# BalanceCar_sch.net
KiCad netlist of a schematic drawn in Altium Designer
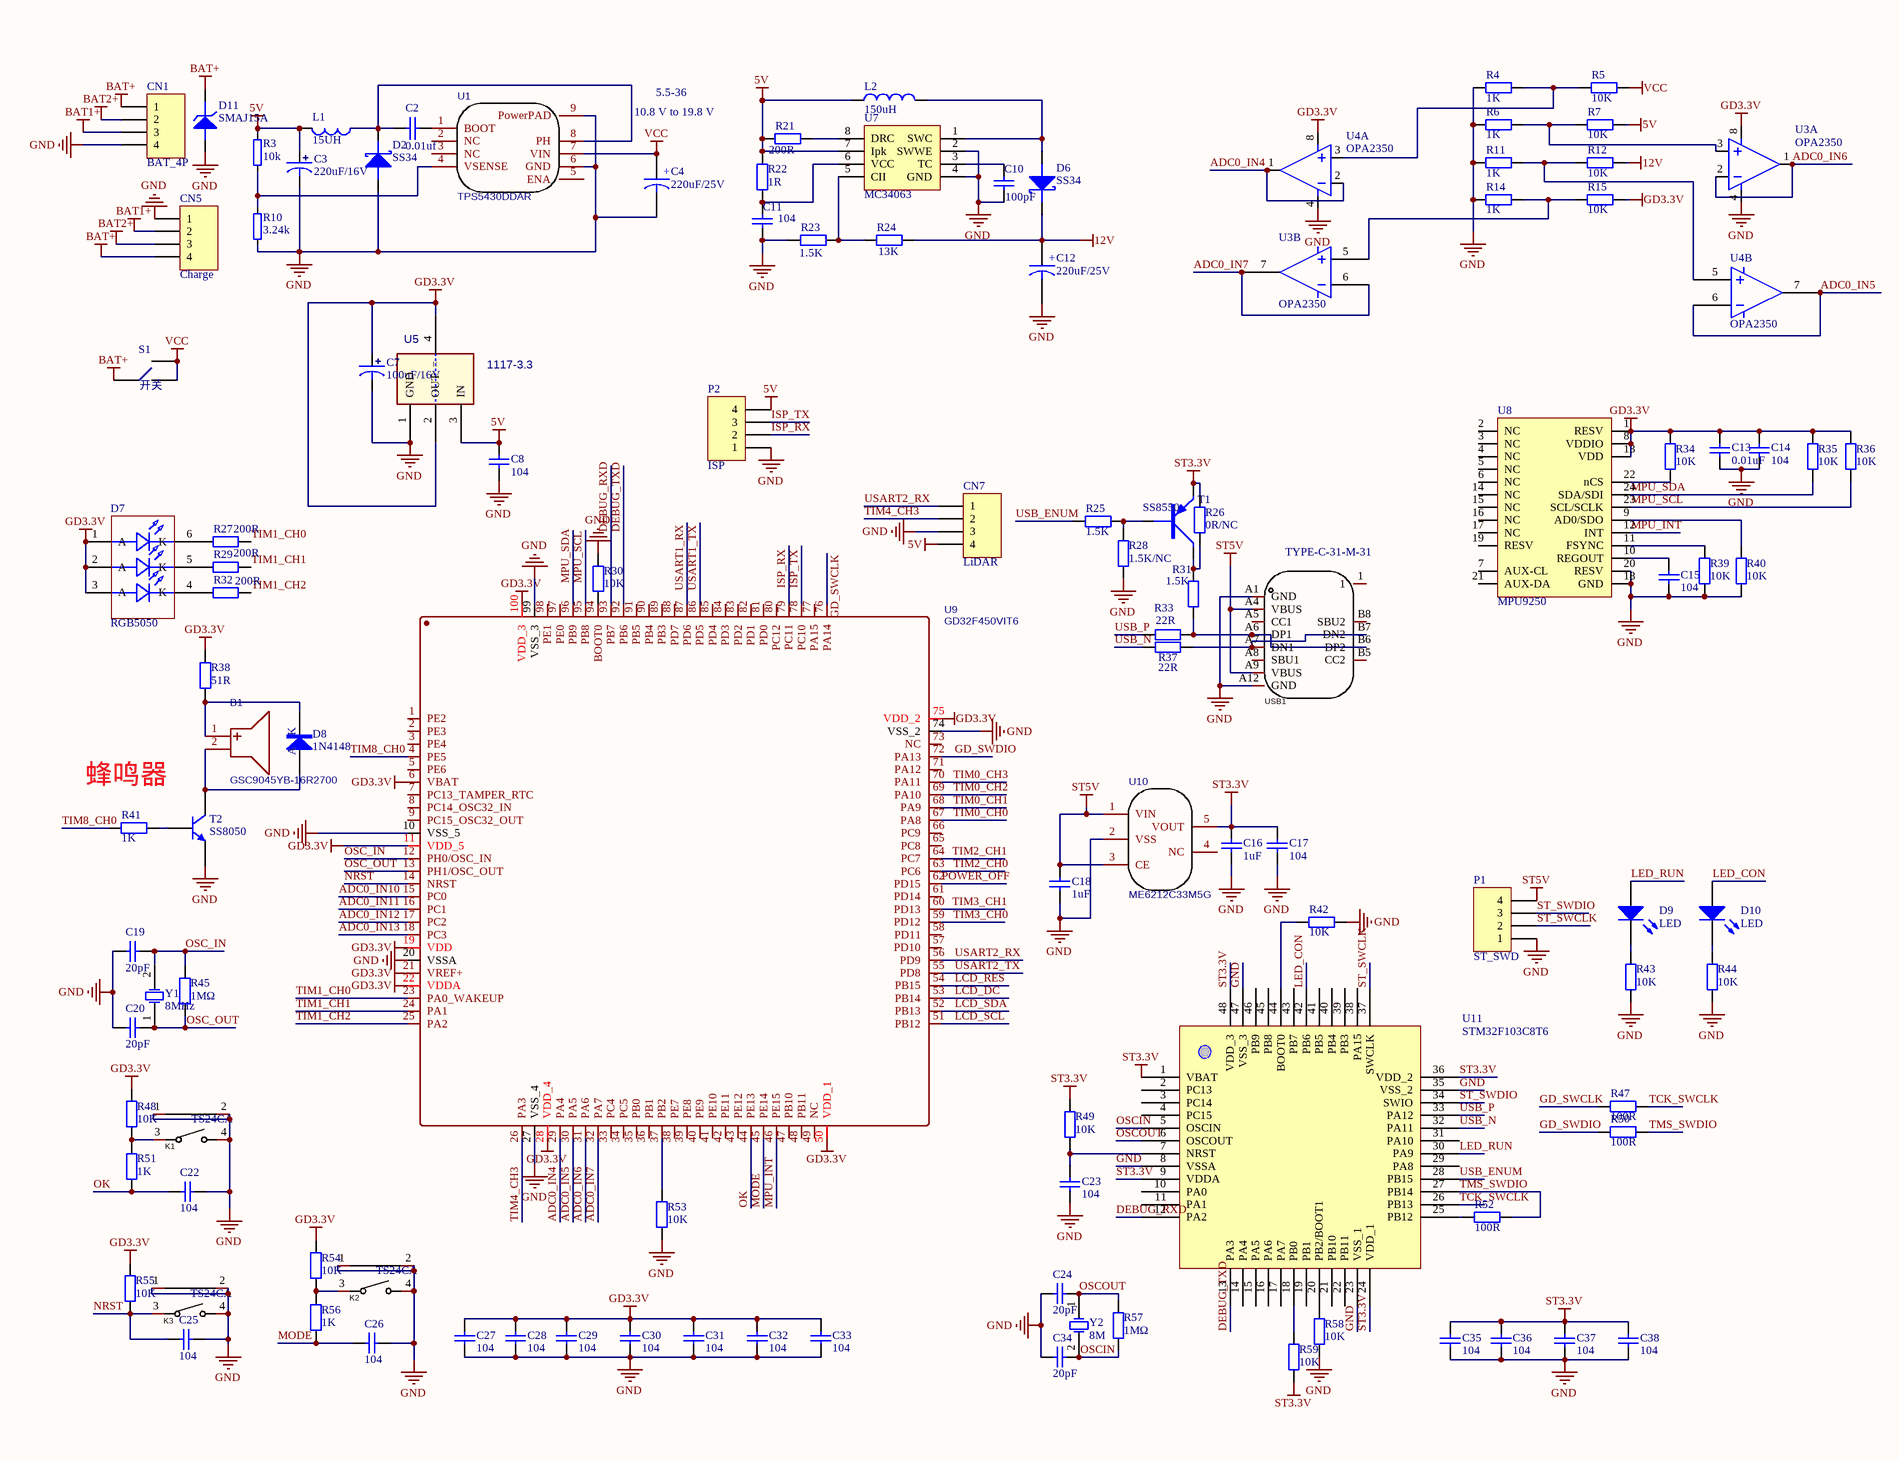
[diagram p0: BalanceCar_sch.SchDoc, left]
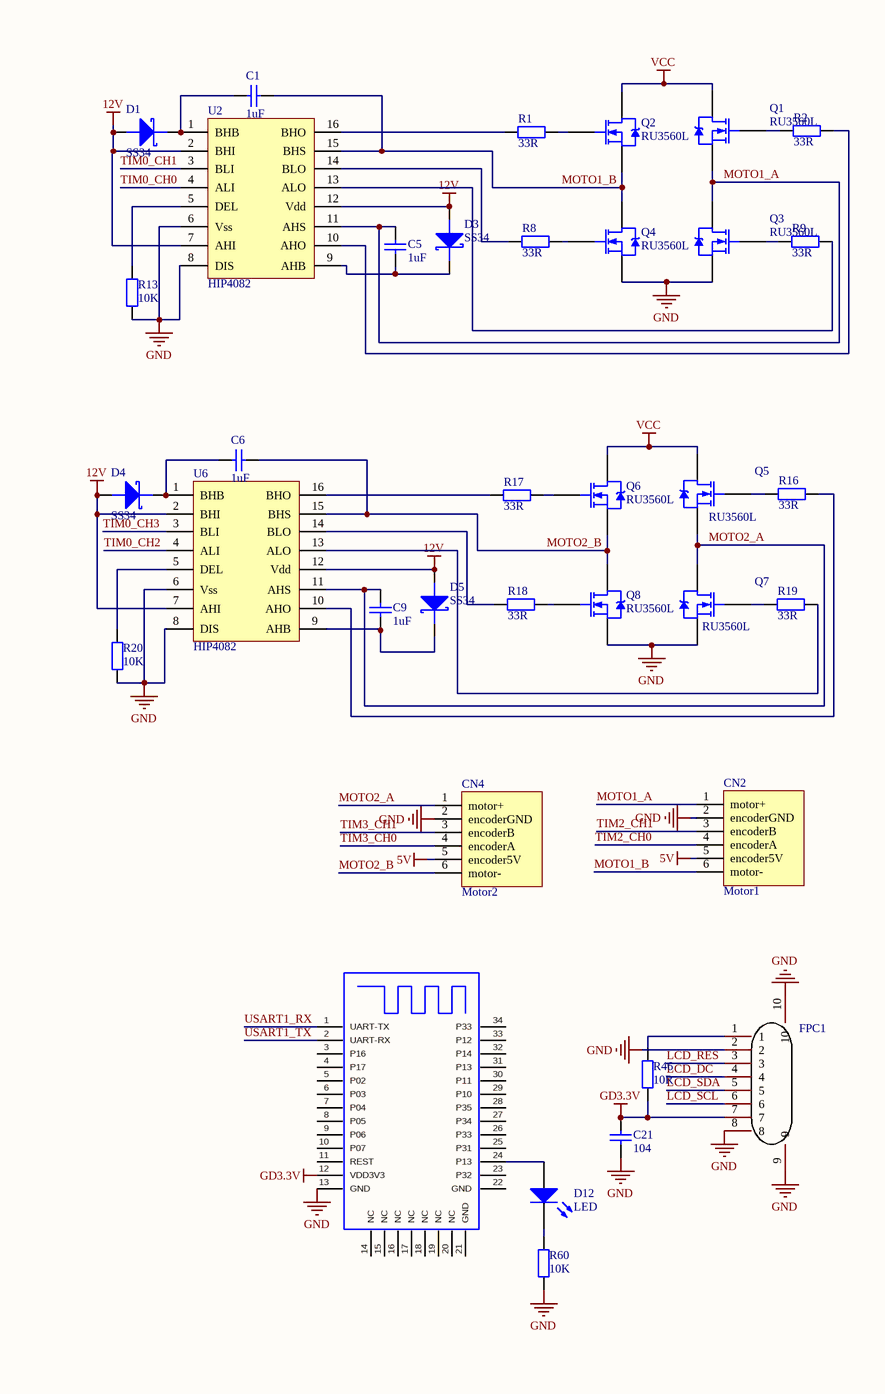
[diagram p1: BalanceCar_sch.SchDoc, right]

(export (version "E")
  (design (tool "Eeschema 10.0.6"))
  (components
    (comp (ref "B1")
      (value "GSC9045YB-16R2700")
      (footprint "BUZ-SMD_GSC9045YB-16R2700")
      (description "无源蜂鸣器")
      (fields (field (name "BOM_SUPPLIER PART") "C255324") (field (name "CONTRIBUTOR") "LCSC"))
      (libsource (lib "1") (part "GSC9045YB-16R2700"))
    )
    (comp (ref "C1")
      (value "1uF")
      (footprint "0603-JLC-C")
      (description "C0603")
      (fields (field (name "PUBLISHER") "Altium Limited"))
      (libsource (lib "Miscellaneous Devices") (part "Cap"))
    )
    (comp (ref "C2")
      (value "0.01uf")
      (footprint "0603-JLC-C")
      (description "C0603")
      (libsource (lib "电容") (part "普通电容"))
    )
    (comp (ref "C3")
      (value "220uF/16V")
      (footprint "SMD,6.3x5.3mm")
      (description "6.3*5.3mm铝电解电容")
      (libsource (lib "电容") (part "SMD_ECAP"))
    )
    (comp (ref "C4")
      (value "220uF/25V")
      (footprint "SMD,6.3x5.8mm")
      (description "贴片铝电解电容SMD,6.3x5.8mm")
      (libsource (lib "*") (part "CAP极性"))
    )
    (comp (ref "C5")
      (value "1uF")
      (footprint "0603-JLC-C")
      (description "C0603")
      (fields (field (name "PUBLISHER") "Altium Limited"))
      (libsource (lib "Miscellaneous Devices") (part "Cap"))
    )
    (comp (ref "C6")
      (value "1uF")
      (footprint "0603-JLC-C")
      (description "C0603")
      (fields (field (name "PUBLISHER") "Altium Limited"))
      (libsource (lib "Miscellaneous Devices") (part "Cap"))
    )
    (comp (ref "C7")
      (value "100uF/16V")
      (footprint "SMD,6.3x5.3mm")
      (description "6.3*5.3mm铝电解电容")
      (libsource (lib "电容") (part "SMD_ECAP"))
    )
    (comp (ref "C8")
      (value "104")
      (footprint "0603-JLC-C")
      (description "C0603")
      (fields (field (name "PUBLISHER") "Altium Limited"))
      (libsource (lib "Miscellaneous Devices") (part "Cap"))
    )
    (comp (ref "C9")
      (value "1uF")
      (footprint "0603-JLC-C")
      (description "C0603")
      (fields (field (name "PUBLISHER") "Altium Limited"))
      (libsource (lib "Miscellaneous Devices") (part "Cap"))
    )
    (comp (ref "C10") (value "100pF") (footprint "0603-JLC-C") (libsource (lib "Luo") (part "CAP_0805")))
    (comp (ref "C11") (value "104") (footprint "0603-JLC-C") (libsource (lib "Luo") (part "CAP_0805")))
    (comp (ref "C12")
      (value "220uF/25V")
      (footprint "SMD,6.3x5.8mm")
      (description "贴片铝电解电容SMD,6.3x5.8mm")
      (libsource (lib "*") (part "CAP极性"))
    )
    (comp (ref "C13")
      (value "0.01uF")
      (footprint "0603-JLC-C")
      (description "C0603")
      (fields (field (name "PUBLISHER") "Altium Limited"))
      (libsource (lib "Miscellaneous Devices") (part "Cap"))
    )
    (comp (ref "C14")
      (value "104")
      (footprint "0603-JLC-C")
      (description "C0603")
      (fields (field (name "PUBLISHER") "Altium Limited"))
      (libsource (lib "Miscellaneous Devices") (part "Cap"))
    )
    (comp (ref "C15")
      (value "104")
      (footprint "0603-JLC-C")
      (description "C0603")
      (fields (field (name "PUBLISHER") "Altium Limited"))
      (libsource (lib "Miscellaneous Devices") (part "Cap"))
    )
    (comp (ref "C16")
      (value "1uF")
      (footprint "0603-JLC-C")
      (description "C0603")
      (fields (field (name "PUBLISHER") "Altium Limited"))
      (libsource (lib "Miscellaneous Devices") (part "Cap"))
    )
    (comp (ref "C17")
      (value "104")
      (footprint "0603-JLC-C")
      (description "C0603")
      (fields (field (name "PUBLISHER") "Altium Limited"))
      (libsource (lib "Miscellaneous Devices") (part "Cap"))
    )
    (comp (ref "C18")
      (value "1uF")
      (footprint "0603-JLC-C")
      (description "C0603")
      (fields (field (name "PUBLISHER") "Altium Limited"))
      (libsource (lib "Miscellaneous Devices") (part "Cap"))
    )
    (comp (ref "C19")
      (value "20pF")
      (footprint "0603-JLC-C")
      (description "C0603")
      (fields (field (name "PUBLISHER") "Altium Limited"))
      (libsource (lib "Miscellaneous Devices") (part "Cap"))
    )
    (comp (ref "C20")
      (value "20pF")
      (footprint "0603-JLC-C")
      (description "C0603")
      (fields (field (name "PUBLISHER") "Altium Limited"))
      (libsource (lib "Miscellaneous Devices") (part "Cap"))
    )
    (comp (ref "C21")
      (value "104")
      (footprint "0603-JLC-C")
      (description "C0603")
      (fields (field (name "PUBLISHER") "Altium Limited"))
      (libsource (lib "Miscellaneous Devices") (part "Cap"))
    )
    (comp (ref "C22")
      (value "104")
      (footprint "0603-JLC-C")
      (description "C0603")
      (fields (field (name "PUBLISHER") "Altium Limited"))
      (libsource (lib "Miscellaneous Devices") (part "Cap"))
    )
    (comp (ref "C23")
      (value "104")
      (footprint "0603-JLC-C")
      (description "C0603")
      (fields (field (name "PUBLISHER") "Altium Limited"))
      (libsource (lib "Miscellaneous Devices") (part "Cap"))
    )
    (comp (ref "C24")
      (value "20pF")
      (footprint "0603-JLC-C")
      (description "C0603")
      (fields (field (name "PUBLISHER") "Altium Limited"))
      (libsource (lib "STM32F103C8T6") (part "Cap"))
    )
    (comp (ref "C25")
      (value "104")
      (footprint "0603-JLC-C")
      (description "C0603")
      (fields (field (name "PUBLISHER") "Altium Limited"))
      (libsource (lib "Miscellaneous Devices") (part "Cap"))
    )
    (comp (ref "C26")
      (value "104")
      (footprint "0603-JLC-C")
      (description "C0603")
      (fields (field (name "PUBLISHER") "Altium Limited"))
      (libsource (lib "Miscellaneous Devices") (part "Cap"))
    )
    (comp (ref "C27")
      (value "104")
      (footprint "0603-JLC-C")
      (description "C0603")
      (fields (field (name "PUBLISHER") "Altium Limited"))
      (libsource (lib "Miscellaneous Devices") (part "Cap"))
    )
    (comp (ref "C28")
      (value "104")
      (footprint "0603-JLC-C")
      (description "C0603")
      (fields (field (name "PUBLISHER") "Altium Limited"))
      (libsource (lib "Miscellaneous Devices") (part "Cap"))
    )
    (comp (ref "C29")
      (value "104")
      (footprint "0603-JLC-C")
      (description "C0603")
      (fields (field (name "PUBLISHER") "Altium Limited"))
      (libsource (lib "Miscellaneous Devices") (part "Cap"))
    )
    (comp (ref "C30")
      (value "104")
      (footprint "0603-JLC-C")
      (description "C0603")
      (fields (field (name "PUBLISHER") "Altium Limited"))
      (libsource (lib "Miscellaneous Devices") (part "Cap"))
    )
    (comp (ref "C31")
      (value "104")
      (footprint "0603-JLC-C")
      (description "C0603")
      (fields (field (name "PUBLISHER") "Altium Limited"))
      (libsource (lib "Miscellaneous Devices") (part "Cap"))
    )
    (comp (ref "C32")
      (value "104")
      (footprint "0603-JLC-C")
      (description "C0603")
      (fields (field (name "PUBLISHER") "Altium Limited"))
      (libsource (lib "Miscellaneous Devices") (part "Cap"))
    )
    (comp (ref "C33")
      (value "104")
      (footprint "0603-JLC-C")
      (description "C0603")
      (fields (field (name "PUBLISHER") "Altium Limited"))
      (libsource (lib "Miscellaneous Devices") (part "Cap"))
    )
    (comp (ref "C34")
      (value "20pF")
      (footprint "0603-JLC-C")
      (description "C0603")
      (fields (field (name "PUBLISHER") "Altium Limited"))
      (libsource (lib "STM32F103C8T6") (part "Cap"))
    )
    (comp (ref "C35")
      (value "104")
      (footprint "0603-JLC-C")
      (description "C0603")
      (fields (field (name "PUBLISHER") "Altium Limited"))
      (libsource (lib "Miscellaneous Devices") (part "Cap"))
    )
    (comp (ref "C36")
      (value "104")
      (footprint "0603-JLC-C")
      (description "C0603")
      (fields (field (name "PUBLISHER") "Altium Limited"))
      (libsource (lib "Miscellaneous Devices") (part "Cap"))
    )
    (comp (ref "C37")
      (value "104")
      (footprint "0603-JLC-C")
      (description "C0603")
      (fields (field (name "PUBLISHER") "Altium Limited"))
      (libsource (lib "Miscellaneous Devices") (part "Cap"))
    )
    (comp (ref "C38")
      (value "104")
      (footprint "0603-JLC-C")
      (description "C0603")
      (fields (field (name "PUBLISHER") "Altium Limited"))
      (libsource (lib "Miscellaneous Devices") (part "Cap"))
    )
    (comp (ref "CN1")
      (value "BAT_4P")
      (footprint "CONN-TH_4P-P2.50_HX25003-4A")
      (description "卧式XH2.54 4P")
      (fields (field (name "PUBLISHER") "Altium Limited"))
      (libsource (lib "Miscellaneous Connectors") (part "Header 4"))
    )
    (comp (ref "CN2")
      (value "Motor1")
      (footprint "CONN-TH_6P-P2.50_X8821WR-06S-N2SN")
      (description "卧式XH2.54 6P")
      (libsource (lib "Schlib1") (part "Motor"))
    )
    (comp (ref "CN4")
      (value "Motor2")
      (footprint "CONN-TH_6P-P2.50_X8821WR-06S-N2SN")
      (description "卧式XH2.54 6P")
      (libsource (lib "Schlib1") (part "Motor"))
    )
    (comp (ref "CN5")
      (value "Charge")
      (footprint "CONN-TH_4P-P2.54_X8821WR-06S-N2SN")
      (description "卧式XH2.54 4P")
      (fields (field (name "PUBLISHER") "Altium Limited"))
      (libsource (lib "Miscellaneous Connectors") (part "Header 4"))
    )
    (comp (ref "CN7")
      (value "LiDAR")
      (footprint "CONN-TH_4P-P2.50_HX25003-4A")
      (description "卧式XH2.54 4P")
      (fields (field (name "PUBLISHER") "Altium Limited"))
      (libsource (lib "Miscellaneous Connectors") (part "Header 4"))
    )
    (comp (ref "D1")
      (value "SS34")
      (footprint "SMA(DO-214AC)")
      (description "肖特基二极管")
      (libsource (lib "二极管") (part "DIODE SCHOTTKY"))
    )
    (comp (ref "D2")
      (value "SS34")
      (footprint "SMA(DO-214AC)")
      (description "肖特基二极管")
      (libsource (lib "二极管") (part "DIODE SCHOTTKY"))
    )
    (comp (ref "D3")
      (value "SS34")
      (footprint "SMA(DO-214AC)")
      (description "肖特基二极管")
      (libsource (lib "二极管") (part "DIODE SCHOTTKY"))
    )
    (comp (ref "D4")
      (value "SS34")
      (footprint "SMA(DO-214AC)")
      (description "肖特基二极管")
      (libsource (lib "二极管") (part "DIODE SCHOTTKY"))
    )
    (comp (ref "D5")
      (value "SS34")
      (footprint "SMA(DO-214AC)")
      (description "肖特基二极管")
      (libsource (lib "二极管") (part "DIODE SCHOTTKY"))
    )
    (comp (ref "D6")
      (value "SS34")
      (footprint "SMA(DO-214AC)")
      (description "肖特基二极管")
      (libsource (lib "二极管") (part "DIODE SCHOTTKY"))
    )
    (comp (ref "D7")
      (value "RGB5050")
      (footprint "LED-SMD_6P-L5.0-W5.0-FD")
      (description "5050灯珠")
      (libsource (lib "Pathfinder_pcb") (part "RGB5050"))
    )
    (comp (ref "D8")
      (value "1N4148")
      (footprint "1206")
      (description "Diode")
      (libsource (lib "*") (part "DIODE"))
    )
    (comp (ref "D9")
      (value "LED")
      (footprint "0603LED")
      (description "0603白色LED")
      (fields (field (name "PUBLISHER") "Altium Limited"))
      (libsource (lib "running car pcb") (part "LED3"))
    )
    (comp (ref "D10")
      (value "LED")
      (footprint "0603LED")
      (description "0603白色LED")
      (fields (field (name "PUBLISHER") "Altium Limited"))
      (libsource (lib "running car pcb") (part "LED3"))
    )
    (comp (ref "D11")
      (value "SMAJ15A")
      (footprint "SMA(DO-214AC)")
      (description "单向TVS管")
      (libsource (lib "Pathfinder_pcb") (part "DIODE ZENER"))
    )
    (comp (ref "D12")
      (value "LED")
      (footprint "0603LED")
      (description "0603白色LED")
      (fields (field (name "PUBLISHER") "Altium Limited"))
      (libsource (lib "running car pcb") (part "LED3"))
    )
    (comp (ref "FPC1")
      (value "AFC24-S08FIC-00")
      (footprint "FPC-SMD_P0.50-8P-QCHF-SM-H2.0")
      (description "间距:0.5mm;触点数量:8;锁定特性:翻盖式;安装类型:卧贴;触点类型:双侧触点/上下接;")
      (fields (field (name "MANUFACTURER") "JS(钜硕电子)"))
      (libsource (lib "altium-import") (part "root_0_AFC24-S08FIC-00_"))
    )
    (comp (ref "K1")
      (value "TS24CA")
      (footprint "SW-SMD_TS24CA")
      (fields (field (name "MANUFACTURER") "SHOU HAN(首韩)"))
      (libsource (lib "TS24CA1_TS24CA") (part "TS24CA"))
    )
    (comp (ref "K2")
      (value "TS24CA")
      (footprint "SW-SMD_TS24CA")
      (fields (field (name "MANUFACTURER") "SHOU HAN(首韩)"))
      (libsource (lib "TS24CA1_TS24CA") (part "TS24CA"))
    )
    (comp (ref "K3")
      (value "TS24CA")
      (footprint "SW-SMD_TS24CA")
      (fields (field (name "MANUFACTURER") "SHOU HAN(首韩)"))
      (libsource (lib "TS24CA1_TS24CA") (part "TS24CA"))
    )
    (comp (ref "L1")
      (value "15UH")
      (footprint "IND-SMD_L7.1-W6.6")
      (description "一体成型功率电感")
      (libsource (lib "常用元件库") (part "L"))
    )
    (comp (ref "L2")
      (value "150uH")
      (footprint "IND-SMD_L5.0-W5.0_SMNR5040")
      (description "Inductor")
      (fields (field (name "PUBLISHER") "Altium Limited"))
      (libsource (lib "Luo") (part "Inductor"))
    )
    (comp (ref "P1")
      (value "ST_SWD")
      (footprint "HDR1X4")
      (description "Header, 4-Pin")
      (fields (field (name "PUBLISHER") "Altium Limited"))
      (libsource (lib "") (part "Header 4_1"))
    )
    (comp (ref "P2")
      (value "ISP")
      (footprint "HDR1X4")
      (description "Header, 4-Pin")
      (fields (field (name "PUBLISHER") "Altium Limited"))
      (libsource (lib "") (part "Header 4_1"))
    )
    (comp (ref "Q1")
      (value "RU3560L")
      (footprint "TO-252-3L")
      (description "NMOSFET")
      (fields
        (field (name "MANUFACTURER") "International Rectifier")
        (field (name "PUBLISHER") "Altium Limited")
      )
      (libsource (lib "DMESC_1") (part "IRFR1205"))
    )
    (comp (ref "Q2")
      (value "RU3560L")
      (footprint "TO-252-3L")
      (description "NMOSFET")
      (fields
        (field (name "MANUFACTURER") "International Rectifier")
        (field (name "PUBLISHER") "Altium Limited")
      )
      (libsource (lib "DMESC_1") (part "IRFR1205"))
    )
    (comp (ref "Q3")
      (value "RU3560L")
      (footprint "TO-252-3L")
      (description "NMOSFET")
      (fields
        (field (name "MANUFACTURER") "International Rectifier")
        (field (name "PUBLISHER") "Altium Limited")
      )
      (libsource (lib "DMESC_1") (part "IRFR1205"))
    )
    (comp (ref "Q4")
      (value "RU3560L")
      (footprint "TO-252-3L")
      (description "NMOSFET")
      (fields
        (field (name "MANUFACTURER") "International Rectifier")
        (field (name "PUBLISHER") "Altium Limited")
      )
      (libsource (lib "DMESC_1") (part "IRFR1205"))
    )
    (comp (ref "Q5")
      (value "RU3560L")
      (footprint "TO-252-3L")
      (description "NMOSFET")
      (fields
        (field (name "MANUFACTURER") "International Rectifier")
        (field (name "PUBLISHER") "Altium Limited")
      )
      (libsource (lib "DMESC_1") (part "IRFR1205"))
    )
    (comp (ref "Q6")
      (value "RU3560L")
      (footprint "TO-252-3L")
      (description "NMOSFET")
      (fields
        (field (name "MANUFACTURER") "International Rectifier")
        (field (name "PUBLISHER") "Altium Limited")
      )
      (libsource (lib "DMESC_1") (part "IRFR1205"))
    )
    (comp (ref "Q7")
      (value "RU3560L")
      (footprint "TO-252-3L")
      (description "NMOSFET")
      (fields
        (field (name "MANUFACTURER") "International Rectifier")
        (field (name "PUBLISHER") "Altium Limited")
      )
      (libsource (lib "DMESC_1") (part "IRFR1205"))
    )
    (comp (ref "Q8")
      (value "RU3560L")
      (footprint "TO-252-3L")
      (description "NMOSFET")
      (fields
        (field (name "MANUFACTURER") "International Rectifier")
        (field (name "PUBLISHER") "Altium Limited")
      )
      (libsource (lib "DMESC_1") (part "IRFR1205"))
    )
    (comp (ref "R1")
      (value "33R")
      (footprint "0603-RMOS")
      (description "R0603")
      (fields (field (name "PUBLISHER") "Altium Limited"))
      (libsource (lib "") (part "Res2_3"))
    )
    (comp (ref "R2")
      (value "33R")
      (footprint "0603-RMOS")
      (description "R0603")
      (fields (field (name "PUBLISHER") "Altium Limited"))
      (libsource (lib "") (part "Res2_3"))
    )
    (comp (ref "R3")
      (value "10k")
      (footprint "0603-JLC-R")
      (description "R0603")
      (libsource (lib "电阻") (part "RES"))
    )
    (comp (ref "R4")
      (value "1K")
      (footprint "0603-JLC-R")
      (description "R0603")
      (fields (field (name "PUBLISHER") "Altium Limited"))
      (libsource (lib "Miscellaneous Devices") (part "Res2"))
    )
    (comp (ref "R5")
      (value "10K")
      (footprint "0603-JLC-R")
      (description "R0603")
      (fields (field (name "PUBLISHER") "Altium Limited"))
      (libsource (lib "Miscellaneous Devices") (part "Res2"))
    )
    (comp (ref "R6")
      (value "1K")
      (footprint "0603-JLC-R")
      (description "R0603")
      (fields (field (name "PUBLISHER") "Altium Limited"))
      (libsource (lib "Miscellaneous Devices") (part "Res2"))
    )
    (comp (ref "R7")
      (value "10K")
      (footprint "0603-JLC-R")
      (description "R0603")
      (fields (field (name "PUBLISHER") "Altium Limited"))
      (libsource (lib "Miscellaneous Devices") (part "Res2"))
    )
    (comp (ref "R8")
      (value "33R")
      (footprint "0603-RMOS")
      (description "R0603")
      (fields (field (name "PUBLISHER") "Altium Limited"))
      (libsource (lib "") (part "Res2_3"))
    )
    (comp (ref "R9")
      (value "33R")
      (footprint "0603-RMOS")
      (description "R0603")
      (fields (field (name "PUBLISHER") "Altium Limited"))
      (libsource (lib "") (part "Res2_3"))
    )
    (comp (ref "R10")
      (value "3.24k")
      (footprint "0603-JLC-R")
      (description "R0603")
      (libsource (lib "电阻") (part "RES"))
    )
    (comp (ref "R11")
      (value "1K")
      (footprint "0603-JLC-R")
      (description "R0603")
      (fields (field (name "PUBLISHER") "Altium Limited"))
      (libsource (lib "Miscellaneous Devices") (part "Res2"))
    )
    (comp (ref "R12")
      (value "10K")
      (footprint "0603-JLC-R")
      (description "R0603")
      (fields (field (name "PUBLISHER") "Altium Limited"))
      (libsource (lib "Miscellaneous Devices") (part "Res2"))
    )
    (comp (ref "R13")
      (value "10K")
      (footprint "0603-JLC-R")
      (description "R0603")
      (fields (field (name "PUBLISHER") "Altium Limited"))
      (libsource (lib "") (part "Res2_1"))
    )
    (comp (ref "R14")
      (value "1K")
      (footprint "0603-JLC-R")
      (description "R0603")
      (fields (field (name "PUBLISHER") "Altium Limited"))
      (libsource (lib "Miscellaneous Devices") (part "Res2"))
    )
    (comp (ref "R15")
      (value "10K")
      (footprint "0603-JLC-R")
      (description "R0603")
      (fields (field (name "PUBLISHER") "Altium Limited"))
      (libsource (lib "Miscellaneous Devices") (part "Res2"))
    )
    (comp (ref "R16")
      (value "33R")
      (footprint "0603-RMOS")
      (description "R0603")
      (fields (field (name "PUBLISHER") "Altium Limited"))
      (libsource (lib "") (part "Res2_3"))
    )
    (comp (ref "R17")
      (value "33R")
      (footprint "0603-RMOS")
      (description "R0603")
      (fields (field (name "PUBLISHER") "Altium Limited"))
      (libsource (lib "") (part "Res2_3"))
    )
    (comp (ref "R18")
      (value "33R")
      (footprint "0603-RMOS")
      (description "R0603")
      (fields (field (name "PUBLISHER") "Altium Limited"))
      (libsource (lib "") (part "Res2_3"))
    )
    (comp (ref "R19")
      (value "33R")
      (footprint "0603-RMOS")
      (description "R0603")
      (fields (field (name "PUBLISHER") "Altium Limited"))
      (libsource (lib "") (part "Res2_3"))
    )
    (comp (ref "R20")
      (value "10K")
      (footprint "0603-JLC-R")
      (description "R0603")
      (fields (field (name "PUBLISHER") "Altium Limited"))
      (libsource (lib "") (part "Res2_1"))
    )
    (comp (ref "R21") (value "200R") (footprint "0603-JLC-R") (libsource (lib "") (part "RES2_0805_1")))
    (comp (ref "R22") (value "1R") (footprint "0603-JLC-R") (libsource (lib "Luo") (part "RES2_0805")))
    (comp (ref "R23") (value "1.5K") (footprint "0603-JLC-R") (libsource (lib "") (part "RES2_0805_1")))
    (comp (ref "R24") (value "13K") (footprint "0603-JLC-R") (libsource (lib "") (part "RES2_0805_2")))
    (comp (ref "R25")
      (value "1.5K")
      (footprint "0603-JLC-R")
      (description "R0603")
      (fields (field (name "PUBLISHER") "Altium Limited"))
      (libsource (lib "") (part "Res2_1"))
    )
    (comp (ref "R26")
      (value "0R/NC")
      (footprint "0603-JLC-R")
      (description "R0603")
      (fields (field (name "PUBLISHER") "Altium Limited"))
      (libsource (lib "") (part "Res2_3"))
    )
    (comp (ref "R27")
      (value "200R")
      (footprint "0603-JLC-R")
      (description "R0603")
      (fields (field (name "PUBLISHER") "Altium Limited"))
      (libsource (lib "") (part "Res2_3"))
    )
    (comp (ref "R28")
      (value "1.5K/NC")
      (footprint "0603-JLC-R")
      (description "R0603")
      (fields (field (name "PUBLISHER") "Altium Limited"))
      (libsource (lib "") (part "Res2_3"))
    )
    (comp (ref "R29")
      (value "200R")
      (footprint "0603-JLC-R")
      (description "R0603")
      (fields (field (name "PUBLISHER") "Altium Limited"))
      (libsource (lib "") (part "Res2_3"))
    )
    (comp (ref "R30")
      (value "10K")
      (footprint "0603-JLC-R")
      (description "R0603")
      (fields (field (name "PUBLISHER") "Altium Limited"))
      (libsource (lib "") (part "Res2_2"))
    )
    (comp (ref "R31")
      (value "1.5K")
      (footprint "0603-JLC-R")
      (description "R0603")
      (fields (field (name "PUBLISHER") "Altium Limited"))
      (libsource (lib "") (part "Res2_3"))
    )
    (comp (ref "R32")
      (value "200R")
      (footprint "0603-JLC-R")
      (description "R0603")
      (fields (field (name "PUBLISHER") "Altium Limited"))
      (libsource (lib "") (part "Res2_3"))
    )
    (comp (ref "R33")
      (value "22R")
      (footprint "0603-JLC-R")
      (description "R0603")
      (fields (field (name "PUBLISHER") "Altium Limited"))
      (libsource (lib "") (part "Res2_1"))
    )
    (comp (ref "R34")
      (value "10K")
      (footprint "0603-JLC-R")
      (description "R0603")
      (fields (field (name "PUBLISHER") "Altium Limited"))
      (libsource (lib "") (part "Res2_2"))
    )
    (comp (ref "R35")
      (value "10K")
      (footprint "0603-JLC-R")
      (description "R0603")
      (fields (field (name "PUBLISHER") "Altium Limited"))
      (libsource (lib "") (part "Res2_2"))
    )
    (comp (ref "R36")
      (value "10K")
      (footprint "0603-JLC-R")
      (description "R0603")
      (fields (field (name "PUBLISHER") "Altium Limited"))
      (libsource (lib "") (part "Res2_2"))
    )
    (comp (ref "R37")
      (value "22R")
      (footprint "0603-JLC-R")
      (description "R0603")
      (fields (field (name "PUBLISHER") "Altium Limited"))
      (libsource (lib "") (part "Res2_1"))
    )
    (comp (ref "R38")
      (value "51R")
      (footprint "0603-JLC-R")
      (description "R0603")
      (fields (field (name "PUBLISHER") "Altium Limited"))
      (libsource (lib "") (part "Res2_2"))
    )
    (comp (ref "R39")
      (value "10K")
      (footprint "0603-JLC-R")
      (description "R0603")
      (fields (field (name "PUBLISHER") "Altium Limited"))
      (libsource (lib "") (part "Res2_2"))
    )
    (comp (ref "R40")
      (value "10K")
      (footprint "0603-JLC-R")
      (description "R0603")
      (fields (field (name "PUBLISHER") "Altium Limited"))
      (libsource (lib "") (part "Res2_2"))
    )
    (comp (ref "R41")
      (value "1K")
      (footprint "0603-JLC-R")
      (description "R0603")
      (fields (field (name "PUBLISHER") "Altium Limited"))
      (libsource (lib "Miscellaneous Devices") (part "Res2"))
    )
    (comp (ref "R42")
      (value "10K")
      (footprint "0603-JLC-R")
      (description "R0603")
      (fields (field (name "PUBLISHER") "Altium Limited"))
      (libsource (lib "STM32F103C8T6") (part "Res2"))
    )
    (comp (ref "R43")
      (value "10K")
      (footprint "0603-JLC-R")
      (description "R0603")
      (fields (field (name "PUBLISHER") "Altium Limited"))
      (libsource (lib "") (part "Res2_2"))
    )
    (comp (ref "R44")
      (value "10K")
      (footprint "0603-JLC-R")
      (description "R0603")
      (fields (field (name "PUBLISHER") "Altium Limited"))
      (libsource (lib "") (part "Res2_2"))
    )
    (comp (ref "R45")
      (value "1MΩ")
      (footprint "0603-JLC-R")
      (description "R0603")
      (fields (field (name "PUBLISHER") "Altium Limited"))
      (libsource (lib "") (part "Res2_1"))
    )
    (comp (ref "R46")
      (value "10R")
      (footprint "0603-JLC-R")
      (description "R0603")
      (fields (field (name "PUBLISHER") "Altium Limited"))
      (libsource (lib "") (part "Res2_2"))
    )
    (comp (ref "R47")
      (value "100R")
      (footprint "0603-JLC-R")
      (description "R0603")
      (fields (field (name "PUBLISHER") "Altium Limited"))
      (libsource (lib "STM32F103C8T6") (part "Res2"))
    )
    (comp (ref "R48")
      (value "10K")
      (footprint "0603-JLC-R")
      (description "R0603")
      (fields (field (name "PUBLISHER") "Altium Limited"))
      (libsource (lib "") (part "Res2_1"))
    )
    (comp (ref "R49")
      (value "10K")
      (footprint "0603-JLC-R")
      (description "R0603")
      (fields (field (name "PUBLISHER") "Altium Limited"))
      (libsource (lib "") (part "Res2_2"))
    )
    (comp (ref "R50")
      (value "100R")
      (footprint "0603-JLC-R")
      (description "R0603")
      (fields (field (name "PUBLISHER") "Altium Limited"))
      (libsource (lib "STM32F103C8T6") (part "Res2"))
    )
    (comp (ref "R51")
      (value "1K")
      (footprint "0603-JLC-R")
      (description "R0603")
      (fields (field (name "PUBLISHER") "Altium Limited"))
      (libsource (lib "") (part "Res2_2"))
    )
    (comp (ref "R52")
      (value "100R")
      (footprint "0603-JLC-R")
      (description "R0603")
      (fields (field (name "PUBLISHER") "Altium Limited"))
      (libsource (lib "STM32F103C8T6") (part "Res2"))
    )
    (comp (ref "R53")
      (value "10K")
      (footprint "0603-JLC-R")
      (description "R0603")
      (fields (field (name "PUBLISHER") "Altium Limited"))
      (libsource (lib "") (part "Res2_2"))
    )
    (comp (ref "R54")
      (value "10K")
      (footprint "0603-JLC-R")
      (description "R0603")
      (fields (field (name "PUBLISHER") "Altium Limited"))
      (libsource (lib "") (part "Res2_1"))
    )
    (comp (ref "R55")
      (value "10K")
      (footprint "0603-JLC-R")
      (description "R0603")
      (fields (field (name "PUBLISHER") "Altium Limited"))
      (libsource (lib "") (part "Res2_1"))
    )
    (comp (ref "R56")
      (value "1K")
      (footprint "0603-JLC-R")
      (description "R0603")
      (fields (field (name "PUBLISHER") "Altium Limited"))
      (libsource (lib "") (part "Res2_2"))
    )
    (comp (ref "R57")
      (value "1MΩ")
      (footprint "0603-JLC-R")
      (description "R0603")
      (fields (field (name "PUBLISHER") "Altium Limited"))
      (libsource (lib "") (part "Res2_2"))
    )
    (comp (ref "R58")
      (value "10K")
      (footprint "0603-JLC-R")
      (description "R0603")
      (fields (field (name "PUBLISHER") "Altium Limited"))
      (libsource (lib "") (part "Res2_2"))
    )
    (comp (ref "R59")
      (value "10K")
      (footprint "0603-JLC-R")
      (description "R0603")
      (fields (field (name "PUBLISHER") "Altium Limited"))
      (libsource (lib "") (part "Res2_2"))
    )
    (comp (ref "R60")
      (value "10K")
      (footprint "0603-JLC-R")
      (description "R0603")
      (fields (field (name "PUBLISHER") "Altium Limited"))
      (libsource (lib "") (part "Res2_2"))
    )
    (comp (ref "S1") (value "开关") (footprint "拨动电源开关") (libsource (lib "lr7843_new") (part "slide_switch")))
    (comp (ref "T1")
      (value "SS8550")
      (footprint "SOT-23")
      (description "PNP三极管")
      (libsource (lib "三极管") (part "PNP"))
    )
    (comp (ref "T2")
      (value "SS8050")
      (footprint "SOT-23")
      (description "NPN三极管")
      (libsource (lib "DMESC_1") (part "2N3904"))
    )
    (comp (ref "U1")
      (value "TPS5430DDAR")
      (footprint "SOIC-8_L5.0-W4.0-P1.27-LS6.0-BL-EP2.0")
      (description "DCDC降压芯片")
      (fields (field (name "BOM_SUPPLIER PART") "C9864"))
      (libsource (lib "2") (part "TPS5430DDAR"))
    )
    (comp (ref "U2")
      (value "HIP4082")
      (footprint "HIP4082b")
      (description "H桥驱动芯片")
      (libsource (lib "lr7843_new") (part "HIP4082"))
    )
    (comp (ref "U3")
      (value "OPA2350")
      (footprint "SOP_8")
      (description "两路运放芯片")
      (libsource (lib "necktest") (part "OPA2350"))
    )
    (comp (ref "U4")
      (value "OPA2350")
      (footprint "SOP_8")
      (description "两路运放芯片")
      (libsource (lib "necktest") (part "OPA2350"))
    )
    (comp (ref "U5")
      (value "1117-3.3")
      (footprint "SOT223")
      (description "线性稳压3.3V")
      (libsource (lib "altium-import") (part "root_0_1117-3.3_"))
    )
    (comp (ref "U6")
      (value "HIP4082")
      (footprint "HIP4082b")
      (description "H桥驱动芯片")
      (libsource (lib "lr7843_new") (part "HIP4082"))
    )
    (comp (ref "U7")
      (value "MC34063")
      (footprint "SOP-8_L4.9-W3.9-P1.27-LS6.0-BL")
      (libsource (lib "Luo") (part "MC34063"))
    )
    (comp (ref "U8") (value "MPU9250") (footprint "QFN24 4x4") (libsource (lib "MPU9250") (part "MPU9250")))
    (comp (ref "U9")
      (value "GD32F450VIT6")
      (footprint "LQFP-100_L14.0-W14.0-P0.50-LS16.0-BL")
      (description "单片机")
      (fields (field (name "BOM_SUPPLIER PART") "C98441"))
      (libsource (lib "Sheet_1_2022-03-03") (part "GD32F450VIT6"))
    )
    (comp (ref "U10")
      (value "ME6212C33M5G")
      (footprint "ME6212C33M5G")
      (description "线性稳压3.3V")
      (fields (field (name "BOM_SUPPLIER PART") "C81233"))
      (libsource (lib "Sheet_1_2021-08-16") (part "ME6212C33M5G"))
    )
    (comp (ref "U11")
      (value "STM32F103C8T6")
      (footprint "STM32F103C6T6")
      (description "单片机")
      (libsource (lib "STM32F103C8T6") (part "STM32F103C8T6"))
    )
    (comp (ref "U13")
      (value "BT04-E01")
      (footprint "BT04-E02")
      (libsource (lib "BT04-E02_原理图封装") (part "BT04-E01"))
    )
    (comp (ref "USB1")
      (value "TYPE-C-31-M-31")
      (footprint "USB-C-SMD_TYPE-C-31-M-31")
      (fields (field (name "MANUFACTURER") "韩国韩荣"))
      (libsource (lib "TYPE-C-31-M-311_TYPE-C-31-M-31") (part "TYPE-C-31-M-31"))
    )
    (comp (ref "Y1")
      (value "8MHz")
      (footprint "3225")
      (description "贴片无源晶振")
      (fields (field (name "PUBLISHER") "Altium Limited"))
      (libsource (lib "Miscellaneous Devices") (part "XTAL"))
    )
    (comp (ref "Y2")
      (value "8M")
      (footprint "3225")
      (description "贴片无源晶振")
      (fields (field (name "PUBLISHER") "Altium Limited"))
      (libsource (lib "STM32F103C8T6") (part "XTAL"))
    )
  )
  (nets
    (net (code "1") (name "/ADC0_IN4") (class "Default")
      (node (ref "U4") (pin "1") (pintype "passive"))
      (node (ref "U4") (pin "2") (pintype "passive"))
      (node (ref "U9") (pin "29") (pinfunction "PA4_29") (pintype "passive"))
    )
    (net (code "2") (name "/ADC0_IN5") (class "Default")
      (node (ref "U4") (pin "6") (pintype "passive"))
      (node (ref "U4") (pin "7") (pintype "passive"))
      (node (ref "U9") (pin "30") (pinfunction "PA5_30") (pintype "passive"))
    )
    (net (code "3") (name "/ADC0_IN6") (class "Default")
      (node (ref "U3") (pin "1") (pintype "passive"))
      (node (ref "U3") (pin "2") (pintype "passive"))
      (node (ref "U9") (pin "31") (pinfunction "PA6_31") (pintype "passive"))
    )
    (net (code "4") (name "/ADC0_IN7") (class "Default")
      (node (ref "U3") (pin "6") (pintype "passive"))
      (node (ref "U3") (pin "7") (pintype "passive"))
      (node (ref "U9") (pin "32") (pinfunction "PA7_32") (pintype "passive"))
    )
    (net (code "5") (name "/ADC0_IN10") (class "Default")
      (node (ref "U9") (pin "15") (pinfunction "PC0_15") (pintype "passive"))
    )
    (net (code "6") (name "/ADC0_IN11") (class "Default")
      (node (ref "U9") (pin "16") (pinfunction "PC1_16") (pintype "passive"))
    )
    (net (code "7") (name "/ADC0_IN12") (class "Default")
      (node (ref "U9") (pin "17") (pinfunction "PC2_17") (pintype "passive"))
    )
    (net (code "8") (name "/ADC0_IN13") (class "Default")
      (node (ref "U9") (pin "18") (pinfunction "PC3_18") (pintype "passive"))
    )
    (net (code "9") (name "/DEBUG_RXD") (class "Default")
      (node (ref "U11") (pin "12") (pinfunction "PA2_12") (pintype "passive"))
      (node (ref "U9") (pin "93") (pinfunction "PB7_93") (pintype "passive"))
    )
    (net (code "10") (name "/DEBUG_TXD") (class "Default")
      (node (ref "U11") (pin "13") (pinfunction "PA3_13") (pintype "passive"))
      (node (ref "U9") (pin "92") (pinfunction "PB6_92") (pintype "passive"))
    )
    (net (code "11") (name "/GD_SWCLK") (class "Default")
      (node (ref "R47") (pin "1") (pinfunction "1_1") (pintype "passive"))
      (node (ref "U9") (pin "76") (pinfunction "PA14_76") (pintype "passive"))
    )
    (net (code "12") (name "/GD_SWDIO") (class "Default")
      (node (ref "R50") (pin "1") (pinfunction "1_1") (pintype "passive"))
      (node (ref "U9") (pin "72") (pinfunction "PA13_72") (pintype "passive"))
    )
    (net (code "13") (name "/ISP_RX") (class "Default")
      (node (ref "P2") (pin "2") (pinfunction "2_2") (pintype "passive"))
      (node (ref "U9") (pin "79") (pinfunction "PC11_79") (pintype "passive"))
    )
    (net (code "14") (name "/ISP_TX") (class "Default")
      (node (ref "P2") (pin "3") (pinfunction "3_3") (pintype "passive"))
      (node (ref "U9") (pin "78") (pinfunction "PC10_78") (pintype "passive"))
    )
    (net (code "15") (name "/LCD_DC") (class "Default")
      (node (ref "FPC1") (pin "4") (pinfunction "4_4") (pintype "passive"))
      (node (ref "U9") (pin "53") (pinfunction "PB14_53") (pintype "passive"))
    )
    (net (code "16") (name "/LCD_RES") (class "Default")
      (node (ref "FPC1") (pin "3") (pinfunction "3_3") (pintype "passive"))
      (node (ref "U9") (pin "54") (pinfunction "PB15_54") (pintype "passive"))
    )
    (net (code "17") (name "/LCD_SCL") (class "Default")
      (node (ref "FPC1") (pin "6") (pinfunction "6_6") (pintype "passive"))
      (node (ref "U9") (pin "51") (pinfunction "PB12_51") (pintype "passive"))
    )
    (net (code "18") (name "/LCD_SDA") (class "Default")
      (node (ref "FPC1") (pin "5") (pinfunction "5_5") (pintype "passive"))
      (node (ref "U9") (pin "52") (pinfunction "PB13_52") (pintype "passive"))
    )
    (net (code "19") (name "/LED_CON") (class "Default")
      (node (ref "D10") (pin "1") (pinfunction "A_1") (pintype "passive"))
      (node (ref "U11") (pin "42") (pinfunction "PB6_42") (pintype "passive"))
    )
    (net (code "20") (name "/LED_RUN") (class "Default")
      (node (ref "D9") (pin "1") (pinfunction "A_1") (pintype "passive"))
      (node (ref "U11") (pin "30") (pinfunction "PA9_30") (pintype "passive"))
    )
    (net (code "21") (name "/MODE") (class "Default")
      (node (ref "C26") (pin "1") (pinfunction "1_1") (pintype "passive"))
      (node (ref "R56") (pin "2") (pinfunction "2_2") (pintype "passive"))
      (node (ref "U9") (pin "45") (pinfunction "PE14_45") (pintype "passive"))
    )
    (net (code "22") (name "/MOTO1_A") (class "Default")
      (node (ref "C5") (pin "2") (pinfunction "2_2") (pintype "passive"))
      (node (ref "CN2") (pin "1") (pinfunction "motor+_1") (pintype "passive"))
      (node (ref "Q1") (pin "3") (pinfunction "S_3") (pintype "passive"))
      (node (ref "Q3") (pin "2") (pinfunction "D_2") (pintype "passive"))
      (node (ref "U2") (pin "11") (pinfunction "AHS_11") (pintype "passive"))
    )
    (net (code "23") (name "/MOTO1_B") (class "Default")
      (node (ref "C1") (pin "2") (pinfunction "2_2") (pintype "passive"))
      (node (ref "CN2") (pin "6") (pinfunction "motor-_6") (pintype "passive"))
      (node (ref "Q2") (pin "3") (pinfunction "S_3") (pintype "passive"))
      (node (ref "Q4") (pin "2") (pinfunction "D_2") (pintype "passive"))
      (node (ref "U2") (pin "15") (pinfunction "BHS_15") (pintype "passive"))
    )
    (net (code "24") (name "/MOTO2_A") (class "Default")
      (node (ref "C9") (pin "2") (pinfunction "2_2") (pintype "passive"))
      (node (ref "CN4") (pin "1") (pinfunction "motor+_1") (pintype "passive"))
      (node (ref "Q5") (pin "3") (pinfunction "S_3") (pintype "passive"))
      (node (ref "Q7") (pin "2") (pinfunction "D_2") (pintype "passive"))
      (node (ref "U6") (pin "11") (pinfunction "AHS_11") (pintype "passive"))
    )
    (net (code "25") (name "/MOTO2_B") (class "Default")
      (node (ref "C6") (pin "2") (pinfunction "2_2") (pintype "passive"))
      (node (ref "CN4") (pin "6") (pinfunction "motor-_6") (pintype "passive"))
      (node (ref "Q6") (pin "3") (pinfunction "S_3") (pintype "passive"))
      (node (ref "Q8") (pin "2") (pinfunction "D_2") (pintype "passive"))
      (node (ref "U6") (pin "15") (pinfunction "BHS_15") (pintype "passive"))
    )
    (net (code "26") (name "/MPU_INT") (class "Default")
      (node (ref "U8") (pin "12") (pinfunction "INT_12") (pintype "passive"))
      (node (ref "U9") (pin "46") (pinfunction "PE15_46") (pintype "passive"))
    )
    (net (code "27") (name "/MPU_SCL") (class "Default")
      (node (ref "R36") (pin "1") (pinfunction "1_1") (pintype "passive"))
      (node (ref "U8") (pin "23") (pinfunction "SCL/SCLK_23") (pintype "passive"))
      (node (ref "U9") (pin "95") (pinfunction "PB8_95") (pintype "passive"))
    )
    (net (code "28") (name "/MPU_SDA") (class "Default")
      (node (ref "R35") (pin "1") (pinfunction "1_1") (pintype "passive"))
      (node (ref "U8") (pin "24") (pinfunction "SDA/SDI_24") (pintype "passive"))
      (node (ref "U9") (pin "96") (pinfunction "PB9_96") (pintype "passive"))
    )
    (net (code "29") (name "/NRST") (class "Default")
      (node (ref "C25") (pin "1") (pinfunction "1_1") (pintype "passive"))
      (node (ref "K3") (pin "3") (pinfunction "3_3") (pintype "passive"))
      (node (ref "R55") (pin "1") (pinfunction "1_1") (pintype "passive"))
      (node (ref "U9") (pin "14") (pinfunction "NRST_14") (pintype "passive"))
    )
    (net (code "30") (name "/OK") (class "Default")
      (node (ref "C22") (pin "1") (pinfunction "1_1") (pintype "passive"))
      (node (ref "R51") (pin "2") (pinfunction "2_2") (pintype "passive"))
      (node (ref "U9") (pin "44") (pinfunction "PE13_44") (pintype "passive"))
    )
    (net (code "31") (name "/OSCIN") (class "Default")
      (node (ref "C34") (pin "2") (pinfunction "2_2") (pintype "passive"))
      (node (ref "R57") (pin "1") (pinfunction "1_1") (pintype "passive"))
      (node (ref "U11") (pin "5") (pinfunction "OSCIN_5") (pintype "passive"))
      (node (ref "Y2") (pin "2") (pinfunction "2_2") (pintype "passive"))
    )
    (net (code "32") (name "/OSCOUT") (class "Default")
      (node (ref "C24") (pin "2") (pinfunction "2_2") (pintype "passive"))
      (node (ref "R57") (pin "2") (pinfunction "2_2") (pintype "passive"))
      (node (ref "U11") (pin "6") (pinfunction "OSCOUT_6") (pintype "passive"))
      (node (ref "Y2") (pin "1") (pinfunction "1_1") (pintype "passive"))
    )
    (net (code "33") (name "/OSC_IN") (class "Default")
      (node (ref "C19") (pin "2") (pinfunction "2_2") (pintype "passive"))
      (node (ref "R45") (pin "2") (pinfunction "2_2") (pintype "passive"))
      (node (ref "U9") (pin "12") (pinfunction "PH0/OSC_IN_12") (pintype "passive"))
      (node (ref "Y1") (pin "2") (pinfunction "OSC2_2") (pintype "passive"))
    )
    (net (code "34") (name "/OSC_OUT") (class "Default")
      (node (ref "C20") (pin "2") (pinfunction "2_2") (pintype "passive"))
      (node (ref "R45") (pin "1") (pinfunction "1_1") (pintype "passive"))
      (node (ref "U9") (pin "13") (pinfunction "PH1/OSC_OUT_13") (pintype "passive"))
      (node (ref "Y1") (pin "1") (pinfunction "OSC1_1") (pintype "passive"))
    )
    (net (code "35") (name "/POWER_OFF") (class "Default")
      (node (ref "U9") (pin "62") (pinfunction "PD15_62") (pintype "passive"))
    )
    (net (code "36") (name "/ST_SWCLK") (class "Default")
      (node (ref "P1") (pin "2") (pinfunction "2_2") (pintype "passive"))
      (node (ref "U11") (pin "37") (pinfunction "SWCLK_37") (pintype "passive"))
    )
    (net (code "37") (name "/ST_SWDIO") (class "Default")
      (node (ref "P1") (pin "3") (pinfunction "3_3") (pintype "passive"))
      (node (ref "U11") (pin "34") (pinfunction "SWIO_34") (pintype "passive"))
    )
    (net (code "38") (name "/TCK_SWCLK") (class "Default")
      (node (ref "R47") (pin "2") (pinfunction "2_2") (pintype "passive"))
      (node (ref "U11") (pin "26") (pinfunction "PB13_26") (pintype "passive"))
    )
    (net (code "39") (name "/TIM0_CH0") (class "Default")
      (node (ref "U2") (pin "4") (pinfunction "ALI_4") (pintype "passive"))
      (node (ref "U9") (pin "67") (pinfunction "PA8_67") (pintype "passive"))
    )
    (net (code "40") (name "/TIM0_CH1") (class "Default")
      (node (ref "U2") (pin "3") (pinfunction "BLI_3") (pintype "passive"))
      (node (ref "U9") (pin "68") (pinfunction "PA9_68") (pintype "passive"))
    )
    (net (code "41") (name "/TIM0_CH2") (class "Default")
      (node (ref "U6") (pin "4") (pinfunction "ALI_4") (pintype "passive"))
      (node (ref "U9") (pin "69") (pinfunction "PA10_69") (pintype "passive"))
    )
    (net (code "42") (name "/TIM0_CH3") (class "Default")
      (node (ref "U6") (pin "3") (pinfunction "BLI_3") (pintype "passive"))
      (node (ref "U9") (pin "70") (pinfunction "PA11_70") (pintype "passive"))
    )
    (net (code "43") (name "/TIM1_CH0") (class "Default")
      (node (ref "R27") (pin "1") (pinfunction "1_1") (pintype "passive"))
      (node (ref "U9") (pin "23") (pinfunction "PA0_WAKEUP_23") (pintype "passive"))
    )
    (net (code "44") (name "/TIM1_CH1") (class "Default")
      (node (ref "R29") (pin "1") (pinfunction "1_1") (pintype "passive"))
      (node (ref "U9") (pin "24") (pinfunction "PA1_24") (pintype "passive"))
    )
    (net (code "45") (name "/TIM1_CH2") (class "Default")
      (node (ref "R32") (pin "1") (pinfunction "1_1") (pintype "passive"))
      (node (ref "U9") (pin "25") (pinfunction "PA2_25") (pintype "passive"))
    )
    (net (code "46") (name "/TIM2_CH0") (class "Default")
      (node (ref "CN2") (pin "4") (pinfunction "encoderA_4") (pintype "passive"))
      (node (ref "U9") (pin "63") (pinfunction "PC6_63") (pintype "passive"))
    )
    (net (code "47") (name "/TIM2_CH1") (class "Default")
      (node (ref "CN2") (pin "3") (pinfunction "encoderB_3") (pintype "passive"))
      (node (ref "U9") (pin "64") (pinfunction "PC7_64") (pintype "passive"))
    )
    (net (code "48") (name "/TIM3_CH0") (class "Default")
      (node (ref "CN4") (pin "4") (pinfunction "encoderA_4") (pintype "passive"))
      (node (ref "U9") (pin "59") (pinfunction "PD12_59") (pintype "passive"))
    )
    (net (code "49") (name "/TIM3_CH1") (class "Default")
      (node (ref "CN4") (pin "3") (pinfunction "encoderB_3") (pintype "passive"))
      (node (ref "U9") (pin "60") (pinfunction "PD13_60") (pintype "passive"))
    )
    (net (code "50") (name "/TIM4_CH3") (class "Default")
      (node (ref "CN7") (pin "2") (pinfunction "2_2") (pintype "passive"))
      (node (ref "U9") (pin "26") (pinfunction "PA3_26") (pintype "passive"))
    )
    (net (code "51") (name "/TIM8_CH0") (class "Default")
      (node (ref "R41") (pin "1") (pinfunction "1_1") (pintype "passive"))
      (node (ref "U9") (pin "4") (pinfunction "PE5_4") (pintype "passive"))
    )
    (net (code "52") (name "/TMS_SWDIO") (class "Default")
      (node (ref "R50") (pin "2") (pinfunction "2_2") (pintype "passive"))
      (node (ref "R52") (pin "2") (pinfunction "2_2") (pintype "passive"))
      (node (ref "U11") (pin "27") (pinfunction "PB14_27") (pintype "passive"))
    )
    (net (code "53") (name "/USART1_RX") (class "Default")
      (node (ref "U13") (pin "1") (pinfunction "UART-TX_1") (pintype "passive"))
      (node (ref "U9") (pin "87") (pinfunction "PD6_87") (pintype "passive"))
    )
    (net (code "54") (name "/USART1_TX") (class "Default")
      (node (ref "U13") (pin "2") (pinfunction "UART-RX_2") (pintype "passive"))
      (node (ref "U9") (pin "86") (pinfunction "PD5_86") (pintype "passive"))
    )
    (net (code "55") (name "/USART2_RX") (class "Default")
      (node (ref "CN7") (pin "1") (pinfunction "1_1") (pintype "passive"))
      (node (ref "U9") (pin "56") (pinfunction "PD9_56") (pintype "passive"))
    )
    (net (code "56") (name "/USART2_TX") (class "Default")
      (node (ref "U9") (pin "55") (pinfunction "PD8_55") (pintype "passive"))
    )
    (net (code "57") (name "/USB_ENUM") (class "Default")
      (node (ref "R25") (pin "2") (pinfunction "2_2") (pintype "passive"))
      (node (ref "U11") (pin "28") (pinfunction "PB15_28") (pintype "passive"))
    )
    (net (code "58") (name "/USB_N") (class "Default")
      (node (ref "R37") (pin "2") (pinfunction "2_2") (pintype "passive"))
      (node (ref "U11") (pin "32") (pinfunction "PA11_32") (pintype "passive"))
    )
    (net (code "59") (name "/USB_P") (class "Default")
      (node (ref "R33") (pin "2") (pinfunction "2_2") (pintype "passive"))
      (node (ref "U11") (pin "33") (pinfunction "PA12_33") (pintype "passive"))
    )
    (net (code "60") (name "5V") (class "Default")
      (node (ref "C3") (pin "1") (pinfunction "1_1") (pintype "passive"))
      (node (ref "C8") (pin "2") (pinfunction "2_2") (pintype "passive"))
      (node (ref "CN2") (pin "5") (pinfunction "encoder5V_5") (pintype "passive"))
      (node (ref "CN4") (pin "5") (pinfunction "encoder5V_5") (pintype "passive"))
      (node (ref "CN7") (pin "4") (pinfunction "4_4") (pintype "passive"))
      (node (ref "L1") (pin "1") (pinfunction "1_1") (pintype "passive"))
      (node (ref "L2") (pin "1") (pinfunction "1_1") (pintype "passive"))
      (node (ref "P2") (pin "4") (pinfunction "4_4") (pintype "passive"))
      (node (ref "R21") (pin "1") (pinfunction "1_1") (pintype "passive"))
      (node (ref "R22") (pin "2") (pinfunction "2_2") (pintype "passive"))
      (node (ref "R3") (pin "2") (pinfunction "2_2") (pintype "passive"))
      (node (ref "R7") (pin "2") (pinfunction "2_2") (pintype "passive"))
      (node (ref "U5") (pin "3") (pinfunction "IN_3") (pintype "passive"))
      (node (ref "U7") (pin "7") (pinfunction "Ipk_7") (pintype "passive"))
    )
    (net (code "61") (name "12V") (class "Default")
      (node (ref "C12") (pin "1") (pinfunction "1_1") (pintype "passive"))
      (node (ref "D1") (pin "2") (pinfunction "A_2") (pintype "passive"))
      (node (ref "D3") (pin "2") (pinfunction "A_2") (pintype "passive"))
      (node (ref "D4") (pin "2") (pinfunction "A_2") (pintype "passive"))
      (node (ref "D5") (pin "2") (pinfunction "A_2") (pintype "passive"))
      (node (ref "D6") (pin "1") (pinfunction "K_1") (pintype "passive"))
      (node (ref "R12") (pin "2") (pinfunction "2_2") (pintype "passive"))
      (node (ref "R24") (pin "1") (pinfunction "1_1") (pintype "passive"))
      (node (ref "U2") (pin "12") (pinfunction "Vdd_12") (pintype "passive"))
      (node (ref "U2") (pin "2") (pinfunction "BHI_2") (pintype "passive"))
      (node (ref "U2") (pin "7") (pinfunction "AHI_7") (pintype "passive"))
      (node (ref "U6") (pin "12") (pinfunction "Vdd_12") (pintype "passive"))
      (node (ref "U6") (pin "2") (pinfunction "BHI_2") (pintype "passive"))
      (node (ref "U6") (pin "7") (pinfunction "AHI_7") (pintype "passive"))
    )
    (net (code "62") (name "BAT+") (class "Default")
      (node (ref "CN1") (pin "1") (pinfunction "1_1") (pintype "passive"))
      (node (ref "CN5") (pin "4") (pinfunction "4_4") (pintype "passive"))
      (node (ref "D11") (pin "1") (pinfunction "K_1") (pintype "passive"))
      (node (ref "S1") (pin "1") (pinfunction "1_1") (pintype "passive"))
    )
    (net (code "63") (name "BAT1+") (class "Default")
      (node (ref "CN1") (pin "3") (pinfunction "3_3") (pintype "passive"))
      (node (ref "CN5") (pin "2") (pinfunction "2_2") (pintype "passive"))
    )
    (net (code "64") (name "BAT2+") (class "Default")
      (node (ref "CN1") (pin "2") (pinfunction "2_2") (pintype "passive"))
      (node (ref "CN5") (pin "3") (pinfunction "3_3") (pintype "passive"))
    )
    (net (code "65") (name "GD3.3V") (class "Default")
      (node (ref "C13") (pin "2") (pinfunction "2_2") (pintype "passive"))
      (node (ref "C14") (pin "2") (pinfunction "2_2") (pintype "passive"))
      (node (ref "C21") (pin "2") (pinfunction "2_2") (pintype "passive"))
      (node (ref "C27") (pin "2") (pinfunction "2_2") (pintype "passive"))
      (node (ref "C28") (pin "2") (pinfunction "2_2") (pintype "passive"))
      (node (ref "C29") (pin "2") (pinfunction "2_2") (pintype "passive"))
      (node (ref "C30") (pin "2") (pinfunction "2_2") (pintype "passive"))
      (node (ref "C31") (pin "2") (pinfunction "2_2") (pintype "passive"))
      (node (ref "C32") (pin "2") (pinfunction "2_2") (pintype "passive"))
      (node (ref "C33") (pin "2") (pinfunction "2_2") (pintype "passive"))
      (node (ref "C7") (pin "1") (pinfunction "1_1") (pintype "passive"))
      (node (ref "D7") (pin "1") (pinfunction "A_1") (pintype "passive"))
      (node (ref "D7") (pin "2") (pinfunction "A_2") (pintype "passive"))
      (node (ref "D7") (pin "3") (pinfunction "A_3") (pintype "passive"))
      (node (ref "FPC1") (pin "7") (pinfunction "7_7") (pintype "passive"))
      (node (ref "R15") (pin "2") (pinfunction "2_2") (pintype "passive"))
      (node (ref "R34") (pin "2") (pinfunction "2_2") (pintype "passive"))
      (node (ref "R35") (pin "2") (pinfunction "2_2") (pintype "passive"))
      (node (ref "R36") (pin "2") (pinfunction "2_2") (pintype "passive"))
      (node (ref "R38") (pin "1") (pinfunction "1_1") (pintype "passive"))
      (node (ref "R46") (pin "1") (pinfunction "1_1") (pintype "passive"))
      (node (ref "R48") (pin "2") (pinfunction "2_2") (pintype "passive"))
      (node (ref "R54") (pin "2") (pinfunction "2_2") (pintype "passive"))
      (node (ref "R55") (pin "2") (pinfunction "2_2") (pintype "passive"))
      (node (ref "U13") (pin "12") (pinfunction "VDD3V3_12") (pintype "passive"))
      (node (ref "U3") (pin "8") (pintype "passive"))
      (node (ref "U4") (pin "8") (pintype "passive"))
      (node (ref "U5") (pin "2") (pinfunction "OUT_2") (pintype "passive"))
      (node (ref "U5") (pin "4") (pinfunction "=_4") (pintype "passive"))
      (node (ref "U8") (pin "1") (pinfunction "RESV_1") (pintype "passive"))
      (node (ref "U8") (pin "13") (pinfunction "VDD_13") (pintype "passive"))
      (node (ref "U8") (pin "8") (pinfunction "VDDIO_8") (pintype "passive"))
      (node (ref "U9") (pin "100") (pinfunction "VDD_3_100") (pintype "passive"))
      (node (ref "U9") (pin "11") (pinfunction "VDD_5_11") (pintype "passive"))
      (node (ref "U9") (pin "19") (pinfunction "VDD_19") (pintype "passive"))
      (node (ref "U9") (pin "21") (pinfunction "VREF+_21") (pintype "passive"))
      (node (ref "U9") (pin "22") (pinfunction "VDDA_22") (pintype "passive"))
      (node (ref "U9") (pin "28") (pinfunction "VDD_4_28") (pintype "passive"))
      (node (ref "U9") (pin "50") (pinfunction "VDD_1_50") (pintype "passive"))
      (node (ref "U9") (pin "6") (pinfunction "VBAT_6") (pintype "passive"))
      (node (ref "U9") (pin "75") (pinfunction "VDD_2_75") (pintype "passive"))
    )
    (net (code "66") (name "GND") (class "Default")
      (node (ref "C10") (pin "1") (pinfunction "1_1") (pintype "passive"))
      (node (ref "C11") (pin "1") (pinfunction "1_1") (pintype "passive"))
      (node (ref "C12") (pin "2") (pinfunction "2_2") (pintype "passive"))
      (node (ref "C13") (pin "1") (pinfunction "1_1") (pintype "passive"))
      (node (ref "C14") (pin "1") (pinfunction "1_1") (pintype "passive"))
      (node (ref "C15") (pin "1") (pinfunction "1_1") (pintype "passive"))
      (node (ref "C16") (pin "1") (pinfunction "1_1") (pintype "passive"))
      (node (ref "C17") (pin "1") (pinfunction "1_1") (pintype "passive"))
      (node (ref "C18") (pin "1") (pinfunction "1_1") (pintype "passive"))
      (node (ref "C19") (pin "1") (pinfunction "1_1") (pintype "passive"))
      (node (ref "C20") (pin "1") (pinfunction "1_1") (pintype "passive"))
      (node (ref "C21") (pin "1") (pinfunction "1_1") (pintype "passive"))
      (node (ref "C22") (pin "2") (pinfunction "2_2") (pintype "passive"))
      (node (ref "C23") (pin "2") (pinfunction "2_2") (pintype "passive"))
      (node (ref "C24") (pin "1") (pinfunction "1_1") (pintype "passive"))
      (node (ref "C25") (pin "2") (pinfunction "2_2") (pintype "passive"))
      (node (ref "C26") (pin "2") (pinfunction "2_2") (pintype "passive"))
      (node (ref "C27") (pin "1") (pinfunction "1_1") (pintype "passive"))
      (node (ref "C28") (pin "1") (pinfunction "1_1") (pintype "passive"))
      (node (ref "C29") (pin "1") (pinfunction "1_1") (pintype "passive"))
      (node (ref "C3") (pin "2") (pinfunction "2_2") (pintype "passive"))
      (node (ref "C30") (pin "1") (pinfunction "1_1") (pintype "passive"))
      (node (ref "C31") (pin "1") (pinfunction "1_1") (pintype "passive"))
      (node (ref "C32") (pin "1") (pinfunction "1_1") (pintype "passive"))
      (node (ref "C33") (pin "1") (pinfunction "1_1") (pintype "passive"))
      (node (ref "C34") (pin "1") (pinfunction "1_1") (pintype "passive"))
      (node (ref "C35") (pin "1") (pinfunction "1_1") (pintype "passive"))
      (node (ref "C36") (pin "1") (pinfunction "1_1") (pintype "passive"))
      (node (ref "C37") (pin "1") (pinfunction "1_1") (pintype "passive"))
      (node (ref "C38") (pin "1") (pinfunction "1_1") (pintype "passive"))
      (node (ref "C4") (pin "2") (pinfunction "2_2") (pintype "passive"))
      (node (ref "C7") (pin "2") (pinfunction "2_2") (pintype "passive"))
      (node (ref "C8") (pin "1") (pinfunction "1_1") (pintype "passive"))
      (node (ref "CN1") (pin "4") (pinfunction "4_4") (pintype "passive"))
      (node (ref "CN2") (pin "2") (pinfunction "encoderGND_2") (pintype "passive"))
      (node (ref "CN4") (pin "2") (pinfunction "encoderGND_2") (pintype "passive"))
      (node (ref "CN5") (pin "1") (pinfunction "1_1") (pintype "passive"))
      (node (ref "CN7") (pin "3") (pinfunction "3_3") (pintype "passive"))
      (node (ref "D11") (pin "2") (pinfunction "A_2") (pintype "passive"))
      (node (ref "D2") (pin "2") (pinfunction "A_2") (pintype "passive"))
      (node (ref "FPC1") (pin "10") (pinfunction "10_10") (pintype "passive"))
      (node (ref "FPC1") (pin "2") (pinfunction "2_2") (pintype "passive"))
      (node (ref "FPC1") (pin "8") (pinfunction "8_8") (pintype "passive"))
      (node (ref "FPC1") (pin "9") (pinfunction "9_9") (pintype "passive"))
      (node (ref "K1") (pin "1") (pinfunction "1_1") (pintype "passive"))
      (node (ref "K1") (pin "2") (pinfunction "2_2") (pintype "passive"))
      (node (ref "K1") (pin "4") (pinfunction "4_4") (pintype "passive"))
      (node (ref "K2") (pin "1") (pinfunction "1_1") (pintype "passive"))
      (node (ref "K2") (pin "2") (pinfunction "2_2") (pintype "passive"))
      (node (ref "K2") (pin "4") (pinfunction "4_4") (pintype "passive"))
      (node (ref "K3") (pin "1") (pinfunction "1_1") (pintype "passive"))
      (node (ref "K3") (pin "2") (pinfunction "2_2") (pintype "passive"))
      (node (ref "K3") (pin "4") (pinfunction "4_4") (pintype "passive"))
      (node (ref "P1") (pin "1") (pinfunction "1_1") (pintype "passive"))
      (node (ref "P2") (pin "1") (pinfunction "1_1") (pintype "passive"))
      (node (ref "Q3") (pin "3") (pinfunction "S_3") (pintype "passive"))
      (node (ref "Q4") (pin "3") (pinfunction "S_3") (pintype "passive"))
      (node (ref "Q7") (pin "3") (pinfunction "S_3") (pintype "passive"))
      (node (ref "Q8") (pin "3") (pinfunction "S_3") (pintype "passive"))
      (node (ref "R10") (pin "1") (pinfunction "1_1") (pintype "passive"))
      (node (ref "R11") (pin "1") (pinfunction "1_1") (pintype "passive"))
      (node (ref "R13") (pin "1") (pinfunction "1_1") (pintype "passive"))
      (node (ref "R14") (pin "1") (pinfunction "1_1") (pintype "passive"))
      (node (ref "R20") (pin "1") (pinfunction "1_1") (pintype "passive"))
      (node (ref "R23") (pin "1") (pinfunction "1_1") (pintype "passive"))
      (node (ref "R28") (pin "2") (pinfunction "2_2") (pintype "passive"))
      (node (ref "R30") (pin "1") (pinfunction "1_1") (pintype "passive"))
      (node (ref "R39") (pin "1") (pinfunction "1_1") (pintype "passive"))
      (node (ref "R4") (pin "1") (pinfunction "1_1") (pintype "passive"))
      (node (ref "R40") (pin "1") (pinfunction "1_1") (pintype "passive"))
      (node (ref "R42") (pin "2") (pinfunction "2_2") (pintype "passive"))
      (node (ref "R43") (pin "1") (pinfunction "1_1") (pintype "passive"))
      (node (ref "R44") (pin "1") (pinfunction "1_1") (pintype "passive"))
      (node (ref "R53") (pin "2") (pinfunction "2_2") (pintype "passive"))
      (node (ref "R58") (pin "1") (pinfunction "1_1") (pintype "passive"))
      (node (ref "R6") (pin "1") (pinfunction "1_1") (pintype "passive"))
      (node (ref "R60") (pin "1") (pinfunction "1_1") (pintype "passive"))
      (node (ref "T2") (pin "2") (pinfunction "E_2") (pintype "passive"))
      (node (ref "U1") (pin "6") (pinfunction "GND_6") (pintype "passive"))
      (node (ref "U1") (pin "9") (pinfunction "PowerPAD_9") (pintype "passive"))
      (node (ref "U10") (pin "2") (pinfunction "VSS_2") (pintype "passive"))
      (node (ref "U11") (pin "23") (pinfunction "VSS_1_23") (pintype "passive"))
      (node (ref "U11") (pin "35") (pinfunction "VSS_2_35") (pintype "passive"))
      (node (ref "U11") (pin "47") (pinfunction "VSS_3_47") (pintype "passive"))
      (node (ref "U11") (pin "8") (pinfunction "VSSA_8") (pintype "passive"))
      (node (ref "U13") (pin "13") (pinfunction "GND_13") (pintype "passive"))
      (node (ref "U2") (pin "6") (pinfunction "Vss_6") (pintype "passive"))
      (node (ref "U2") (pin "8") (pinfunction "DIS_8") (pintype "passive"))
      (node (ref "U3") (pin "4") (pintype "passive"))
      (node (ref "U4") (pin "4") (pintype "passive"))
      (node (ref "U5") (pin "1") (pinfunction "GND_1") (pintype "passive"))
      (node (ref "U6") (pin "6") (pinfunction "Vss_6") (pintype "passive"))
      (node (ref "U6") (pin "8") (pinfunction "DIS_8") (pintype "passive"))
      (node (ref "U7") (pin "2") (pinfunction "SWWE_2") (pintype "passive"))
      (node (ref "U7") (pin "4") (pinfunction "GND_4") (pintype "passive"))
      (node (ref "U8") (pin "18") (pinfunction "GND_18") (pintype "passive"))
      (node (ref "U8") (pin "20") (pinfunction "RESV_20") (pintype "passive"))
      (node (ref "U9") (pin "10") (pinfunction "VSS_5_10") (pintype "passive"))
      (node (ref "U9") (pin "20") (pinfunction "VSSA_20") (pintype "passive"))
      (node (ref "U9") (pin "27") (pinfunction "VSS_4_27") (pintype "passive"))
      (node (ref "U9") (pin "74") (pinfunction "VSS_2_74") (pintype "passive"))
      (node (ref "U9") (pin "99") (pinfunction "VSS_3_99") (pintype "passive"))
      (node (ref "USB1") (pin "A1") (pinfunction "GND_A1") (pintype "passive"))
      (node (ref "USB1") (pin "A12") (pinfunction "GND_A12") (pintype "passive"))
    )
    (net (code "67") (name "Net-(B1-+)") (class "Default")
      (node (ref "B1") (pin "1") (pinfunction "+_1") (pintype "passive"))
      (node (ref "D8") (pin "2") (pinfunction "K_2") (pintype "passive"))
      (node (ref "R38") (pin "2") (pinfunction "2_2") (pintype "passive"))
    )
    (net (code "68") (name "Net-(B1--)") (class "Default")
      (node (ref "B1") (pin "2") (pinfunction "-_2") (pintype "passive"))
      (node (ref "D8") (pin "1") (pintype "passive"))
      (node (ref "T2") (pin "3") (pinfunction "C_3") (pintype "passive"))
    )
    (net (code "69") (name "Net-(D1-K)") (class "Default")
      (node (ref "C1") (pin "1") (pinfunction "1_1") (pintype "passive"))
      (node (ref "D1") (pin "1") (pinfunction "K_1") (pintype "passive"))
      (node (ref "U2") (pin "1") (pinfunction "BHB_1") (pintype "passive"))
    )
    (net (code "70") (name "Net-(D2-K)") (class "Default")
      (node (ref "C2") (pin "1") (pinfunction "1_1") (pintype "passive"))
      (node (ref "D2") (pin "1") (pinfunction "K_1") (pintype "passive"))
      (node (ref "L1") (pin "2") (pinfunction "2_2") (pintype "passive"))
      (node (ref "U1") (pin "8") (pinfunction "PH_8") (pintype "passive"))
    )
    (net (code "71") (name "Net-(D3-K)") (class "Default")
      (node (ref "C5") (pin "1") (pinfunction "1_1") (pintype "passive"))
      (node (ref "D3") (pin "1") (pinfunction "K_1") (pintype "passive"))
      (node (ref "U2") (pin "9") (pinfunction "AHB_9") (pintype "passive"))
    )
    (net (code "72") (name "Net-(D4-K)") (class "Default")
      (node (ref "C6") (pin "1") (pinfunction "1_1") (pintype "passive"))
      (node (ref "D4") (pin "1") (pinfunction "K_1") (pintype "passive"))
      (node (ref "U6") (pin "1") (pinfunction "BHB_1") (pintype "passive"))
    )
    (net (code "73") (name "Net-(D5-K)") (class "Default")
      (node (ref "C9") (pin "1") (pinfunction "1_1") (pintype "passive"))
      (node (ref "D5") (pin "1") (pinfunction "K_1") (pintype "passive"))
      (node (ref "U6") (pin "9") (pinfunction "AHB_9") (pintype "passive"))
    )
    (net (code "74") (name "Net-(D6-A)") (class "Default")
      (node (ref "D6") (pin "2") (pinfunction "A_2") (pintype "passive"))
      (node (ref "L2") (pin "2") (pinfunction "2_2") (pintype "passive"))
      (node (ref "U7") (pin "1") (pinfunction "SWC_1") (pintype "passive"))
    )
    (net (code "75") (name "Net-(D7-K-Pad4)") (class "Default")
      (node (ref "D7") (pin "4") (pinfunction "K_4") (pintype "passive"))
      (node (ref "R32") (pin "2") (pinfunction "2_2") (pintype "passive"))
    )
    (net (code "76") (name "Net-(D7-K-Pad5)") (class "Default")
      (node (ref "D7") (pin "5") (pinfunction "K_5") (pintype "passive"))
      (node (ref "R29") (pin "2") (pinfunction "2_2") (pintype "passive"))
    )
    (net (code "77") (name "Net-(D7-K-Pad6)") (class "Default")
      (node (ref "D7") (pin "6") (pinfunction "K_6") (pintype "passive"))
      (node (ref "R27") (pin "2") (pinfunction "2_2") (pintype "passive"))
    )
    (net (code "78") (name "Net-(D9-K)") (class "Default")
      (node (ref "D9") (pin "2") (pinfunction "K_2") (pintype "passive"))
      (node (ref "R43") (pin "2") (pinfunction "2_2") (pintype "passive"))
    )
    (net (code "79") (name "Net-(D10-K)") (class "Default")
      (node (ref "D10") (pin "2") (pinfunction "K_2") (pintype "passive"))
      (node (ref "R44") (pin "2") (pinfunction "2_2") (pintype "passive"))
    )
    (net (code "80") (name "Net-(D12-A)") (class "Default")
      (node (ref "D12") (pin "1") (pinfunction "A_1") (pintype "passive"))
      (node (ref "U13") (pin "24") (pinfunction "P13_24") (pintype "passive"))
    )
    (net (code "81") (name "Net-(D12-K)") (class "Default")
      (node (ref "D12") (pin "2") (pinfunction "K_2") (pintype "passive"))
      (node (ref "R60") (pin "2") (pinfunction "2_2") (pintype "passive"))
    )
    (net (code "82") (name "Net-(FPC1-Pad1)") (class "Default")
      (node (ref "FPC1") (pin "1") (pinfunction "1_1") (pintype "passive"))
      (node (ref "R46") (pin "2") (pinfunction "2_2") (pintype "passive"))
    )
    (net (code "83") (name "Net-(K1-Pad3)") (class "Default")
      (node (ref "K1") (pin "3") (pinfunction "3_3") (pintype "passive"))
      (node (ref "R48") (pin "1") (pinfunction "1_1") (pintype "passive"))
      (node (ref "R51") (pin "1") (pinfunction "1_1") (pintype "passive"))
    )
    (net (code "84") (name "Net-(K2-Pad3)") (class "Default")
      (node (ref "K2") (pin "3") (pinfunction "3_3") (pintype "passive"))
      (node (ref "R54") (pin "1") (pinfunction "1_1") (pintype "passive"))
      (node (ref "R56") (pin "1") (pinfunction "1_1") (pintype "passive"))
    )
    (net (code "85") (name "Net-(Q1-G)") (class "Default")
      (node (ref "Q1") (pin "1") (pinfunction "G_1") (pintype "passive"))
      (node (ref "R2") (pin "2") (pinfunction "2_2") (pintype "passive"))
    )
    (net (code "86") (name "Net-(Q2-G)") (class "Default")
      (node (ref "Q2") (pin "1") (pinfunction "G_1") (pintype "passive"))
      (node (ref "R1") (pin "1") (pinfunction "1_1") (pintype "passive"))
    )
    (net (code "87") (name "Net-(Q3-G)") (class "Default")
      (node (ref "Q3") (pin "1") (pinfunction "G_1") (pintype "passive"))
      (node (ref "R9") (pin "2") (pinfunction "2_2") (pintype "passive"))
    )
    (net (code "88") (name "Net-(Q4-G)") (class "Default")
      (node (ref "Q4") (pin "1") (pinfunction "G_1") (pintype "passive"))
      (node (ref "R8") (pin "1") (pinfunction "1_1") (pintype "passive"))
    )
    (net (code "89") (name "Net-(Q5-G)") (class "Default")
      (node (ref "Q5") (pin "1") (pinfunction "G_1") (pintype "passive"))
      (node (ref "R16") (pin "2") (pinfunction "2_2") (pintype "passive"))
    )
    (net (code "90") (name "Net-(Q6-G)") (class "Default")
      (node (ref "Q6") (pin "1") (pinfunction "G_1") (pintype "passive"))
      (node (ref "R17") (pin "1") (pinfunction "1_1") (pintype "passive"))
    )
    (net (code "91") (name "Net-(Q7-G)") (class "Default")
      (node (ref "Q7") (pin "1") (pinfunction "G_1") (pintype "passive"))
      (node (ref "R19") (pin "2") (pinfunction "2_2") (pintype "passive"))
    )
    (net (code "92") (name "Net-(Q8-G)") (class "Default")
      (node (ref "Q8") (pin "1") (pinfunction "G_1") (pintype "passive"))
      (node (ref "R18") (pin "1") (pinfunction "1_1") (pintype "passive"))
    )
    (net (code "93") (name "Net-(R4-Pad2)") (class "Default")
      (node (ref "R4") (pin "2") (pinfunction "2_2") (pintype "passive"))
      (node (ref "R5") (pin "1") (pinfunction "1_1") (pintype "passive"))
      (node (ref "U4") (pin "3") (pintype "passive"))
    )
    (net (code "94") (name "Net-(R6-Pad2)") (class "Default")
      (node (ref "R6") (pin "2") (pinfunction "2_2") (pintype "passive"))
      (node (ref "R7") (pin "1") (pinfunction "1_1") (pintype "passive"))
      (node (ref "U3") (pin "3") (pintype "passive"))
    )
    (net (code "95") (name "Net-(R11-Pad2)") (class "Default")
      (node (ref "R11") (pin "2") (pinfunction "2_2") (pintype "passive"))
      (node (ref "R12") (pin "1") (pinfunction "1_1") (pintype "passive"))
      (node (ref "U4") (pin "5") (pintype "passive"))
    )
    (net (code "96") (name "Net-(R14-Pad2)") (class "Default")
      (node (ref "R14") (pin "2") (pinfunction "2_2") (pintype "passive"))
      (node (ref "R15") (pin "1") (pinfunction "1_1") (pintype "passive"))
      (node (ref "U3") (pin "5") (pintype "passive"))
    )
    (net (code "97") (name "Net-(T1-B)") (class "Default")
      (node (ref "R25") (pin "1") (pinfunction "1_1") (pintype "passive"))
      (node (ref "R28") (pin "1") (pinfunction "1_1") (pintype "passive"))
      (node (ref "T1") (pin "1") (pinfunction "B_1") (pintype "passive"))
    )
    (net (code "98") (name "Net-(T1-C)") (class "Default")
      (node (ref "R26") (pin "2") (pinfunction "2_2") (pintype "passive"))
      (node (ref "R31") (pin "1") (pinfunction "1_1") (pintype "passive"))
      (node (ref "T1") (pin "3") (pinfunction "C_3") (pintype "passive"))
    )
    (net (code "99") (name "Net-(T2-B)") (class "Default")
      (node (ref "R41") (pin "2") (pinfunction "2_2") (pintype "passive"))
      (node (ref "T2") (pin "1") (pinfunction "B_1") (pintype "passive"))
    )
    (net (code "100") (name "Net-(U1-BOOT)") (class "Default")
      (node (ref "C2") (pin "2") (pinfunction "2_2") (pintype "passive"))
      (node (ref "U1") (pin "1") (pinfunction "BOOT_1") (pintype "passive"))
    )
    (net (code "101") (name "Net-(U1-VSENSE)") (class "Default")
      (node (ref "R10") (pin "2") (pinfunction "2_2") (pintype "passive"))
      (node (ref "R3") (pin "1") (pinfunction "1_1") (pintype "passive"))
      (node (ref "U1") (pin "4") (pinfunction "VSENSE_4") (pintype "passive"))
    )
    (net (code "102") (name "Net-(U2-AHO)") (class "Default")
      (node (ref "R2") (pin "1") (pinfunction "1_1") (pintype "passive"))
      (node (ref "U2") (pin "10") (pinfunction "AHO_10") (pintype "passive"))
    )
    (net (code "103") (name "Net-(U2-ALO)") (class "Default")
      (node (ref "R9") (pin "1") (pinfunction "1_1") (pintype "passive"))
      (node (ref "U2") (pin "13") (pinfunction "ALO_13") (pintype "passive"))
    )
    (net (code "104") (name "Net-(U2-BHO)") (class "Default")
      (node (ref "R1") (pin "2") (pinfunction "2_2") (pintype "passive"))
      (node (ref "U2") (pin "16") (pinfunction "BHO_16") (pintype "passive"))
    )
    (net (code "105") (name "Net-(U2-BLO)") (class "Default")
      (node (ref "R8") (pin "2") (pinfunction "2_2") (pintype "passive"))
      (node (ref "U2") (pin "14") (pinfunction "BLO_14") (pintype "passive"))
    )
    (net (code "106") (name "Net-(U2-DEL)") (class "Default")
      (node (ref "R13") (pin "2") (pinfunction "2_2") (pintype "passive"))
      (node (ref "U2") (pin "5") (pinfunction "DEL_5") (pintype "passive"))
    )
    (net (code "107") (name "Net-(U6-AHO)") (class "Default")
      (node (ref "R16") (pin "1") (pinfunction "1_1") (pintype "passive"))
      (node (ref "U6") (pin "10") (pinfunction "AHO_10") (pintype "passive"))
    )
    (net (code "108") (name "Net-(U6-ALO)") (class "Default")
      (node (ref "R19") (pin "1") (pinfunction "1_1") (pintype "passive"))
      (node (ref "U6") (pin "13") (pinfunction "ALO_13") (pintype "passive"))
    )
    (net (code "109") (name "Net-(U6-BHO)") (class "Default")
      (node (ref "R17") (pin "2") (pinfunction "2_2") (pintype "passive"))
      (node (ref "U6") (pin "16") (pinfunction "BHO_16") (pintype "passive"))
    )
    (net (code "110") (name "Net-(U6-BLO)") (class "Default")
      (node (ref "R18") (pin "2") (pinfunction "2_2") (pintype "passive"))
      (node (ref "U6") (pin "14") (pinfunction "BLO_14") (pintype "passive"))
    )
    (net (code "111") (name "Net-(U6-DEL)") (class "Default")
      (node (ref "R20") (pin "2") (pinfunction "2_2") (pintype "passive"))
      (node (ref "U6") (pin "5") (pinfunction "DEL_5") (pintype "passive"))
    )
    (net (code "112") (name "Net-(U7-CII)") (class "Default")
      (node (ref "R23") (pin "2") (pinfunction "2_2") (pintype "passive"))
      (node (ref "R24") (pin "2") (pinfunction "2_2") (pintype "passive"))
      (node (ref "U7") (pin "5") (pinfunction "CII_5") (pintype "passive"))
    )
    (net (code "113") (name "Net-(U7-DRC)") (class "Default")
      (node (ref "R21") (pin "2") (pinfunction "2_2") (pintype "passive"))
      (node (ref "U7") (pin "8") (pinfunction "DRC_8") (pintype "passive"))
    )
    (net (code "114") (name "Net-(U7-TC)") (class "Default")
      (node (ref "C10") (pin "2") (pinfunction "2_2") (pintype "passive"))
      (node (ref "U7") (pin "3") (pinfunction "TC_3") (pintype "passive"))
    )
    (net (code "115") (name "Net-(U7-VCC)") (class "Default")
      (node (ref "C11") (pin "2") (pinfunction "2_2") (pintype "passive"))
      (node (ref "R22") (pin "1") (pinfunction "1_1") (pintype "passive"))
      (node (ref "U7") (pin "6") (pinfunction "VCC_6") (pintype "passive"))
    )
    (net (code "116") (name "Net-(U8-AD0{slash}SDO)") (class "Default")
      (node (ref "R40") (pin "2") (pinfunction "2_2") (pintype "passive"))
      (node (ref "U8") (pin "9") (pinfunction "AD0/SDO_9") (pintype "passive"))
    )
    (net (code "117") (name "Net-(U8-FSYNC)") (class "Default")
      (node (ref "R39") (pin "2") (pinfunction "2_2") (pintype "passive"))
      (node (ref "U8") (pin "11") (pinfunction "FSYNC_11") (pintype "passive"))
    )
    (net (code "118") (name "Net-(U8-REGOUT)") (class "Default")
      (node (ref "C15") (pin "2") (pinfunction "2_2") (pintype "passive"))
      (node (ref "U8") (pin "10") (pinfunction "REGOUT_10") (pintype "passive"))
    )
    (net (code "119") (name "Net-(U8-nCS)") (class "Default")
      (node (ref "R34") (pin "1") (pinfunction "1_1") (pintype "passive"))
      (node (ref "U8") (pin "22") (pinfunction "nCS_22") (pintype "passive"))
    )
    (net (code "120") (name "Net-(U9-BOOT0)") (class "Default")
      (node (ref "R30") (pin "2") (pinfunction "2_2") (pintype "passive"))
      (node (ref "U9") (pin "94") (pinfunction "BOOT0_94") (pintype "passive"))
    )
    (net (code "121") (name "Net-(U9-PB2)") (class "Default")
      (node (ref "R53") (pin "1") (pinfunction "1_1") (pintype "passive"))
      (node (ref "U9") (pin "37") (pinfunction "PB2_37") (pintype "passive"))
    )
    (net (code "122") (name "Net-(U11-BOOT0)") (class "Default")
      (node (ref "R42") (pin "1") (pinfunction "1_1") (pintype "passive"))
      (node (ref "U11") (pin "44") (pinfunction "BOOT0_44") (pintype "passive"))
    )
    (net (code "123") (name "Net-(U11-NRST)") (class "Default")
      (node (ref "C23") (pin "1") (pinfunction "1_1") (pintype "passive"))
      (node (ref "R49") (pin "1") (pinfunction "1_1") (pintype "passive"))
      (node (ref "U11") (pin "7") (pinfunction "NRST_7") (pintype "passive"))
    )
    (net (code "124") (name "Net-(U11-PB0)") (class "Default")
      (node (ref "R59") (pin "2") (pinfunction "2_2") (pintype "passive"))
      (node (ref "U11") (pin "18") (pinfunction "PB0_18") (pintype "passive"))
    )
    (net (code "125") (name "Net-(U11-PB2{slash}BOOT1)") (class "Default")
      (node (ref "R58") (pin "2") (pinfunction "2_2") (pintype "passive"))
      (node (ref "U11") (pin "20") (pinfunction "PB2/BOOT1_20") (pintype "passive"))
    )
    (net (code "126") (name "Net-(U11-PB12)") (class "Default")
      (node (ref "R52") (pin "1") (pinfunction "1_1") (pintype "passive"))
      (node (ref "U11") (pin "25") (pinfunction "PB12_25") (pintype "passive"))
    )
    (net (code "127") (name "Net-(USB1-DN1)") (class "Default")
      (node (ref "R37") (pin "1") (pinfunction "1_1") (pintype "passive"))
      (node (ref "USB1") (pin "A7") (pinfunction "DN1_A7") (pintype "passive"))
      (node (ref "USB1") (pin "B7") (pinfunction "DN2_B7") (pintype "passive"))
    )
    (net (code "128") (name "Net-(USB1-DP1)") (class "Default")
      (node (ref "R31") (pin "2") (pinfunction "2_2") (pintype "passive"))
      (node (ref "R33") (pin "1") (pinfunction "1_1") (pintype "passive"))
      (node (ref "USB1") (pin "A6") (pinfunction "DP1_A6") (pintype "passive"))
      (node (ref "USB1") (pin "B6") (pinfunction "DP2_B6") (pintype "passive"))
    )
    (net (code "129") (name "ST3.3V") (class "Default")
      (node (ref "C16") (pin "2") (pinfunction "2_2") (pintype "passive"))
      (node (ref "C17") (pin "2") (pinfunction "2_2") (pintype "passive"))
      (node (ref "C35") (pin "2") (pinfunction "2_2") (pintype "passive"))
      (node (ref "C36") (pin "2") (pinfunction "2_2") (pintype "passive"))
      (node (ref "C37") (pin "2") (pinfunction "2_2") (pintype "passive"))
      (node (ref "C38") (pin "2") (pinfunction "2_2") (pintype "passive"))
      (node (ref "R26") (pin "1") (pinfunction "1_1") (pintype "passive"))
      (node (ref "R49") (pin "2") (pinfunction "2_2") (pintype "passive"))
      (node (ref "R59") (pin "1") (pinfunction "1_1") (pintype "passive"))
      (node (ref "T1") (pin "2") (pinfunction "E_2") (pintype "passive"))
      (node (ref "U10") (pin "5") (pinfunction "VOUT_5") (pintype "passive"))
      (node (ref "U11") (pin "1") (pinfunction "VBAT_1") (pintype "passive"))
      (node (ref "U11") (pin "24") (pinfunction "VDD_1_24") (pintype "passive"))
      (node (ref "U11") (pin "36") (pinfunction "VDD_2_36") (pintype "passive"))
      (node (ref "U11") (pin "48") (pinfunction "VDD_3_48") (pintype "passive"))
      (node (ref "U11") (pin "9") (pinfunction "VDDA_9") (pintype "passive"))
    )
    (net (code "130") (name "ST5V") (class "Default")
      (node (ref "C18") (pin "2") (pinfunction "2_2") (pintype "passive"))
      (node (ref "P1") (pin "4") (pinfunction "4_4") (pintype "passive"))
      (node (ref "U10") (pin "1") (pinfunction "VIN_1") (pintype "passive"))
      (node (ref "U10") (pin "3") (pinfunction "CE_3") (pintype "passive"))
      (node (ref "USB1") (pin "A4") (pinfunction "VBUS_A4") (pintype "passive"))
      (node (ref "USB1") (pin "A9") (pinfunction "VBUS_A9") (pintype "passive"))
    )
    (net (code "131") (name "VCC") (class "Default")
      (node (ref "C4") (pin "1") (pinfunction "1_1") (pintype "passive"))
      (node (ref "Q1") (pin "2") (pinfunction "D_2") (pintype "passive"))
      (node (ref "Q2") (pin "2") (pinfunction "D_2") (pintype "passive"))
      (node (ref "Q5") (pin "2") (pinfunction "D_2") (pintype "passive"))
      (node (ref "Q6") (pin "2") (pinfunction "D_2") (pintype "passive"))
      (node (ref "R5") (pin "2") (pinfunction "2_2") (pintype "passive"))
      (node (ref "S1") (pin "2") (pinfunction "2_2") (pintype "passive"))
      (node (ref "S1") (pin "3") (pinfunction "3_3") (pintype "passive"))
      (node (ref "U1") (pin "7") (pinfunction "VIN_7") (pintype "passive"))
    )
    (net (code "132") (name "unconnected-(U1-ENA-Pad5)") (class "Default")
      (node (ref "U1") (pin "5") (pinfunction "ENA_5") (pintype "passive"))
    )
    (net (code "133") (name "unconnected-(U1-NC-Pad2)") (class "Default")
      (node (ref "U1") (pin "2") (pinfunction "NC_2") (pintype "passive"))
    )
    (net (code "134") (name "unconnected-(U1-NC-Pad3)") (class "Default")
      (node (ref "U1") (pin "3") (pinfunction "NC_3") (pintype "passive"))
    )
    (net (code "135") (name "unconnected-(U8-AUX-CL-Pad7)") (class "Default")
      (node (ref "U8") (pin "7") (pinfunction "AUX-CL_7") (pintype "passive"))
    )
    (net (code "136") (name "unconnected-(U8-AUX-DA-Pad21)") (class "Default")
      (node (ref "U8") (pin "21") (pinfunction "AUX-DA_21") (pintype "passive"))
    )
    (net (code "137") (name "unconnected-(U8-NC-Pad2)") (class "Default")
      (node (ref "U8") (pin "2") (pinfunction "NC_2") (pintype "passive"))
    )
    (net (code "138") (name "unconnected-(U8-NC-Pad3)") (class "Default")
      (node (ref "U8") (pin "3") (pinfunction "NC_3") (pintype "passive"))
    )
    (net (code "139") (name "unconnected-(U8-NC-Pad4)") (class "Default")
      (node (ref "U8") (pin "4") (pinfunction "NC_4") (pintype "passive"))
    )
    (net (code "140") (name "unconnected-(U8-NC-Pad5)") (class "Default")
      (node (ref "U8") (pin "5") (pinfunction "NC_5") (pintype "passive"))
    )
    (net (code "141") (name "unconnected-(U8-NC-Pad6)") (class "Default")
      (node (ref "U8") (pin "6") (pinfunction "NC_6") (pintype "passive"))
    )
    (net (code "142") (name "unconnected-(U8-NC-Pad14)") (class "Default")
      (node (ref "U8") (pin "14") (pinfunction "NC_14") (pintype "passive"))
    )
    (net (code "143") (name "unconnected-(U8-NC-Pad15)") (class "Default")
      (node (ref "U8") (pin "15") (pinfunction "NC_15") (pintype "passive"))
    )
    (net (code "144") (name "unconnected-(U8-NC-Pad16)") (class "Default")
      (node (ref "U8") (pin "16") (pinfunction "NC_16") (pintype "passive"))
    )
    (net (code "145") (name "unconnected-(U8-NC-Pad17)") (class "Default")
      (node (ref "U8") (pin "17") (pinfunction "NC_17") (pintype "passive"))
    )
    (net (code "146") (name "unconnected-(U8-RESV-Pad19)") (class "Default")
      (node (ref "U8") (pin "19") (pinfunction "RESV_19") (pintype "passive"))
    )
    (net (code "147") (name "unconnected-(U9-NC-Pad49)") (class "Default")
      (node (ref "U9") (pin "49") (pinfunction "NC_49") (pintype "passive"))
    )
    (net (code "148") (name "unconnected-(U9-NC-Pad73)") (class "Default")
      (node (ref "U9") (pin "73") (pinfunction "NC_73") (pintype "passive"))
    )
    (net (code "149") (name "unconnected-(U9-PA12-Pad71)") (class "Default")
      (node (ref "U9") (pin "71") (pinfunction "PA12_71") (pintype "passive"))
    )
    (net (code "150") (name "unconnected-(U9-PA15-Pad77)") (class "Default")
      (node (ref "U9") (pin "77") (pinfunction "PA15_77") (pintype "passive"))
    )
    (net (code "151") (name "unconnected-(U9-PB0-Pad35)") (class "Default")
      (node (ref "U9") (pin "35") (pinfunction "PB0_35") (pintype "passive"))
    )
    (net (code "152") (name "unconnected-(U9-PB1-Pad36)") (class "Default")
      (node (ref "U9") (pin "36") (pinfunction "PB1_36") (pintype "passive"))
    )
    (net (code "153") (name "unconnected-(U9-PB3-Pad89)") (class "Default")
      (node (ref "U9") (pin "89") (pinfunction "PB3_89") (pintype "passive"))
    )
    (net (code "154") (name "unconnected-(U9-PB4-Pad90)") (class "Default")
      (node (ref "U9") (pin "90") (pinfunction "PB4_90") (pintype "passive"))
    )
    (net (code "155") (name "unconnected-(U9-PB5-Pad91)") (class "Default")
      (node (ref "U9") (pin "91") (pinfunction "PB5_91") (pintype "passive"))
    )
    (net (code "156") (name "unconnected-(U9-PB10-Pad47)") (class "Default")
      (node (ref "U9") (pin "47") (pinfunction "PB10_47") (pintype "passive"))
    )
    (net (code "157") (name "unconnected-(U9-PB11-Pad48)") (class "Default")
      (node (ref "U9") (pin "48") (pinfunction "PB11_48") (pintype "passive"))
    )
    (net (code "158") (name "unconnected-(U9-PC4-Pad33)") (class "Default")
      (node (ref "U9") (pin "33") (pinfunction "PC4_33") (pintype "passive"))
    )
    (net (code "159") (name "unconnected-(U9-PC5-Pad34)") (class "Default")
      (node (ref "U9") (pin "34") (pinfunction "PC5_34") (pintype "passive"))
    )
    (net (code "160") (name "unconnected-(U9-PC8-Pad65)") (class "Default")
      (node (ref "U9") (pin "65") (pinfunction "PC8_65") (pintype "passive"))
    )
    (net (code "161") (name "unconnected-(U9-PC9-Pad66)") (class "Default")
      (node (ref "U9") (pin "66") (pinfunction "PC9_66") (pintype "passive"))
    )
    (net (code "162") (name "unconnected-(U9-PC12-Pad80)") (class "Default")
      (node (ref "U9") (pin "80") (pinfunction "PC12_80") (pintype "passive"))
    )
    (net (code "163") (name "unconnected-(U9-PC13_TAMPER_RTC-Pad7)") (class "Default")
      (node (ref "U9") (pin "7") (pinfunction "PC13_TAMPER_RTC_7") (pintype "passive"))
    )
    (net (code "164") (name "unconnected-(U9-PC14_OSC32_IN-Pad8)") (class "Default")
      (node (ref "U9") (pin "8") (pinfunction "PC14_OSC32_IN_8") (pintype "passive"))
    )
    (net (code "165") (name "unconnected-(U9-PC15_OSC32_OUT-Pad9)") (class "Default")
      (node (ref "U9") (pin "9") (pinfunction "PC15_OSC32_OUT_9") (pintype "passive"))
    )
    (net (code "166") (name "unconnected-(U9-PD0-Pad81)") (class "Default")
      (node (ref "U9") (pin "81") (pinfunction "PD0_81") (pintype "passive"))
    )
    (net (code "167") (name "unconnected-(U9-PD1-Pad82)") (class "Default")
      (node (ref "U9") (pin "82") (pinfunction "PD1_82") (pintype "passive"))
    )
    (net (code "168") (name "unconnected-(U9-PD2-Pad83)") (class "Default")
      (node (ref "U9") (pin "83") (pinfunction "PD2_83") (pintype "passive"))
    )
    (net (code "169") (name "unconnected-(U9-PD3-Pad84)") (class "Default")
      (node (ref "U9") (pin "84") (pinfunction "PD3_84") (pintype "passive"))
    )
    (net (code "170") (name "unconnected-(U9-PD4-Pad85)") (class "Default")
      (node (ref "U9") (pin "85") (pinfunction "PD4_85") (pintype "passive"))
    )
    (net (code "171") (name "unconnected-(U9-PD7-Pad88)") (class "Default")
      (node (ref "U9") (pin "88") (pinfunction "PD7_88") (pintype "passive"))
    )
    (net (code "172") (name "unconnected-(U9-PD10-Pad57)") (class "Default")
      (node (ref "U9") (pin "57") (pinfunction "PD10_57") (pintype "passive"))
    )
    (net (code "173") (name "unconnected-(U9-PD11-Pad58)") (class "Default")
      (node (ref "U9") (pin "58") (pinfunction "PD11_58") (pintype "passive"))
    )
    (net (code "174") (name "unconnected-(U9-PD14-Pad61)") (class "Default")
      (node (ref "U9") (pin "61") (pinfunction "PD14_61") (pintype "passive"))
    )
    (net (code "175") (name "unconnected-(U9-PE0-Pad97)") (class "Default")
      (node (ref "U9") (pin "97") (pinfunction "PE0_97") (pintype "passive"))
    )
    (net (code "176") (name "unconnected-(U9-PE1-Pad98)") (class "Default")
      (node (ref "U9") (pin "98") (pinfunction "PE1_98") (pintype "passive"))
    )
    (net (code "177") (name "unconnected-(U9-PE2-Pad1)") (class "Default")
      (node (ref "U9") (pin "1") (pinfunction "PE2_1") (pintype "passive"))
    )
    (net (code "178") (name "unconnected-(U9-PE3-Pad2)") (class "Default")
      (node (ref "U9") (pin "2") (pinfunction "PE3_2") (pintype "passive"))
    )
    (net (code "179") (name "unconnected-(U9-PE4-Pad3)") (class "Default")
      (node (ref "U9") (pin "3") (pinfunction "PE4_3") (pintype "passive"))
    )
    (net (code "180") (name "unconnected-(U9-PE6-Pad5)") (class "Default")
      (node (ref "U9") (pin "5") (pinfunction "PE6_5") (pintype "passive"))
    )
    (net (code "181") (name "unconnected-(U9-PE7-Pad38)") (class "Default")
      (node (ref "U9") (pin "38") (pinfunction "PE7_38") (pintype "passive"))
    )
    (net (code "182") (name "unconnected-(U9-PE8-Pad39)") (class "Default")
      (node (ref "U9") (pin "39") (pinfunction "PE8_39") (pintype "passive"))
    )
    (net (code "183") (name "unconnected-(U9-PE9-Pad40)") (class "Default")
      (node (ref "U9") (pin "40") (pinfunction "PE9_40") (pintype "passive"))
    )
    (net (code "184") (name "unconnected-(U9-PE10-Pad41)") (class "Default")
      (node (ref "U9") (pin "41") (pinfunction "PE10_41") (pintype "passive"))
    )
    (net (code "185") (name "unconnected-(U9-PE11-Pad42)") (class "Default")
      (node (ref "U9") (pin "42") (pinfunction "PE11_42") (pintype "passive"))
    )
    (net (code "186") (name "unconnected-(U9-PE12-Pad43)") (class "Default")
      (node (ref "U9") (pin "43") (pinfunction "PE12_43") (pintype "passive"))
    )
    (net (code "187") (name "unconnected-(U10-NC-Pad4)") (class "Default")
      (node (ref "U10") (pin "4") (pinfunction "NC_4") (pintype "passive"))
    )
    (net (code "188") (name "unconnected-(U11-PA0-Pad10)") (class "Default")
      (node (ref "U11") (pin "10") (pinfunction "PA0_10") (pintype "passive"))
    )
    (net (code "189") (name "unconnected-(U11-PA1-Pad11)") (class "Default")
      (node (ref "U11") (pin "11") (pinfunction "PA1_11") (pintype "passive"))
    )
    (net (code "190") (name "unconnected-(U11-PA4-Pad14)") (class "Default")
      (node (ref "U11") (pin "14") (pinfunction "PA4_14") (pintype "passive"))
    )
    (net (code "191") (name "unconnected-(U11-PA5-Pad15)") (class "Default")
      (node (ref "U11") (pin "15") (pinfunction "PA5_15") (pintype "passive"))
    )
    (net (code "192") (name "unconnected-(U11-PA6-Pad16)") (class "Default")
      (node (ref "U11") (pin "16") (pinfunction "PA6_16") (pintype "passive"))
    )
    (net (code "193") (name "unconnected-(U11-PA7-Pad17)") (class "Default")
      (node (ref "U11") (pin "17") (pinfunction "PA7_17") (pintype "passive"))
    )
    (net (code "194") (name "unconnected-(U11-PA8-Pad29)") (class "Default")
      (node (ref "U11") (pin "29") (pinfunction "PA8_29") (pintype "passive"))
    )
    (net (code "195") (name "unconnected-(U11-PA10-Pad31)") (class "Default")
      (node (ref "U11") (pin "31") (pinfunction "PA10_31") (pintype "passive"))
    )
    (net (code "196") (name "unconnected-(U11-PA15-Pad38)") (class "Default")
      (node (ref "U11") (pin "38") (pinfunction "PA15_38") (pintype "passive"))
    )
    (net (code "197") (name "unconnected-(U11-PB1-Pad19)") (class "Default")
      (node (ref "U11") (pin "19") (pinfunction "PB1_19") (pintype "passive"))
    )
    (net (code "198") (name "unconnected-(U11-PB3-Pad39)") (class "Default")
      (node (ref "U11") (pin "39") (pinfunction "PB3_39") (pintype "passive"))
    )
    (net (code "199") (name "unconnected-(U11-PB4-Pad40)") (class "Default")
      (node (ref "U11") (pin "40") (pinfunction "PB4_40") (pintype "passive"))
    )
    (net (code "200") (name "unconnected-(U11-PB5-Pad41)") (class "Default")
      (node (ref "U11") (pin "41") (pinfunction "PB5_41") (pintype "passive"))
    )
    (net (code "201") (name "unconnected-(U11-PB7-Pad43)") (class "Default")
      (node (ref "U11") (pin "43") (pinfunction "PB7_43") (pintype "passive"))
    )
    (net (code "202") (name "unconnected-(U11-PB8-Pad45)") (class "Default")
      (node (ref "U11") (pin "45") (pinfunction "PB8_45") (pintype "passive"))
    )
    (net (code "203") (name "unconnected-(U11-PB9-Pad46)") (class "Default")
      (node (ref "U11") (pin "46") (pinfunction "PB9_46") (pintype "passive"))
    )
    (net (code "204") (name "unconnected-(U11-PB10-Pad21)") (class "Default")
      (node (ref "U11") (pin "21") (pinfunction "PB10_21") (pintype "passive"))
    )
    (net (code "205") (name "unconnected-(U11-PB11-Pad22)") (class "Default")
      (node (ref "U11") (pin "22") (pinfunction "PB11_22") (pintype "passive"))
    )
    (net (code "206") (name "unconnected-(U11-PC13-Pad2)") (class "Default")
      (node (ref "U11") (pin "2") (pinfunction "PC13_2") (pintype "passive"))
    )
    (net (code "207") (name "unconnected-(U11-PC14-Pad3)") (class "Default")
      (node (ref "U11") (pin "3") (pinfunction "PC14_3") (pintype "passive"))
    )
    (net (code "208") (name "unconnected-(U11-PC15-Pad4)") (class "Default")
      (node (ref "U11") (pin "4") (pinfunction "PC15_4") (pintype "passive"))
    )
    (net (code "209") (name "unconnected-(U13-GND-Pad21)") (class "Default")
      (node (ref "U13") (pin "21") (pinfunction "GND_21") (pintype "passive"))
    )
    (net (code "210") (name "unconnected-(U13-GND-Pad22)") (class "Default")
      (node (ref "U13") (pin "22") (pinfunction "GND_22") (pintype "passive"))
    )
    (net (code "211") (name "unconnected-(U13-NC-Pad14)") (class "Default")
      (node (ref "U13") (pin "14") (pinfunction "NC_14") (pintype "passive"))
    )
    (net (code "212") (name "unconnected-(U13-NC-Pad15)") (class "Default")
      (node (ref "U13") (pin "15") (pinfunction "NC_15") (pintype "passive"))
    )
    (net (code "213") (name "unconnected-(U13-NC-Pad16)") (class "Default")
      (node (ref "U13") (pin "16") (pinfunction "NC_16") (pintype "passive"))
    )
    (net (code "214") (name "unconnected-(U13-NC-Pad17)") (class "Default")
      (node (ref "U13") (pin "17") (pinfunction "NC_17") (pintype "passive"))
    )
    (net (code "215") (name "unconnected-(U13-NC-Pad18)") (class "Default")
      (node (ref "U13") (pin "18") (pinfunction "NC_18") (pintype "passive"))
    )
    (net (code "216") (name "unconnected-(U13-NC-Pad19)") (class "Default")
      (node (ref "U13") (pin "19") (pinfunction "NC_19") (pintype "passive"))
    )
    (net (code "217") (name "unconnected-(U13-NC-Pad20)") (class "Default")
      (node (ref "U13") (pin "20") (pinfunction "NC_20") (pintype "passive"))
    )
    (net (code "218") (name "unconnected-(U13-P02-Pad5)") (class "Default")
      (node (ref "U13") (pin "5") (pinfunction "P02_5") (pintype "passive"))
    )
    (net (code "219") (name "unconnected-(U13-P03-Pad6)") (class "Default")
      (node (ref "U13") (pin "6") (pinfunction "P03_6") (pintype "passive"))
    )
    (net (code "220") (name "unconnected-(U13-P04-Pad7)") (class "Default")
      (node (ref "U13") (pin "7") (pinfunction "P04_7") (pintype "passive"))
    )
    (net (code "221") (name "unconnected-(U13-P05-Pad8)") (class "Default")
      (node (ref "U13") (pin "8") (pinfunction "P05_8") (pintype "passive"))
    )
    (net (code "222") (name "unconnected-(U13-P06-Pad9)") (class "Default")
      (node (ref "U13") (pin "9") (pinfunction "P06_9") (pintype "passive"))
    )
    (net (code "223") (name "unconnected-(U13-P07-Pad10)") (class "Default")
      (node (ref "U13") (pin "10") (pinfunction "P07_10") (pintype "passive"))
    )
    (net (code "224") (name "unconnected-(U13-P10-Pad29)") (class "Default")
      (node (ref "U13") (pin "29") (pinfunction "P10_29") (pintype "passive"))
    )
    (net (code "225") (name "unconnected-(U13-P11-Pad30)") (class "Default")
      (node (ref "U13") (pin "30") (pinfunction "P11_30") (pintype "passive"))
    )
    (net (code "226") (name "unconnected-(U13-P12-Pad33)") (class "Default")
      (node (ref "U13") (pin "33") (pinfunction "P12_33") (pintype "passive"))
    )
    (net (code "227") (name "unconnected-(U13-P13-Pad31)") (class "Default")
      (node (ref "U13") (pin "31") (pinfunction "P13_31") (pintype "passive"))
    )
    (net (code "228") (name "unconnected-(U13-P14-Pad32)") (class "Default")
      (node (ref "U13") (pin "32") (pinfunction "P14_32") (pintype "passive"))
    )
    (net (code "229") (name "unconnected-(U13-P16-Pad3)") (class "Default")
      (node (ref "U13") (pin "3") (pinfunction "P16_3") (pintype "passive"))
    )
    (net (code "230") (name "unconnected-(U13-P17-Pad4)") (class "Default")
      (node (ref "U13") (pin "4") (pinfunction "P17_4") (pintype "passive"))
    )
    (net (code "231") (name "unconnected-(U13-P31-Pad25)") (class "Default")
      (node (ref "U13") (pin "25") (pinfunction "P31_25") (pintype "passive"))
    )
    (net (code "232") (name "unconnected-(U13-P32-Pad23)") (class "Default")
      (node (ref "U13") (pin "23") (pinfunction "P32_23") (pintype "passive"))
    )
    (net (code "233") (name "unconnected-(U13-P33-Pad26)") (class "Default")
      (node (ref "U13") (pin "26") (pinfunction "P33_26") (pintype "passive"))
    )
    (net (code "234") (name "unconnected-(U13-P33-Pad34)") (class "Default")
      (node (ref "U13") (pin "34") (pinfunction "P33_34") (pintype "passive"))
    )
    (net (code "235") (name "unconnected-(U13-P34-Pad27)") (class "Default")
      (node (ref "U13") (pin "27") (pinfunction "P34_27") (pintype "passive"))
    )
    (net (code "236") (name "unconnected-(U13-P35-Pad28)") (class "Default")
      (node (ref "U13") (pin "28") (pinfunction "P35_28") (pintype "passive"))
    )
    (net (code "237") (name "unconnected-(U13-REST-Pad11)") (class "Default")
      (node (ref "U13") (pin "11") (pinfunction "REST_11") (pintype "passive"))
    )
    (net (code "238") (name "unconnected-(USB1-CC1-PadA5)") (class "Default")
      (node (ref "USB1") (pin "A5") (pinfunction "CC1_A5") (pintype "passive"))
    )
    (net (code "239") (name "unconnected-(USB1-CC2-PadB5)") (class "Default")
      (node (ref "USB1") (pin "B5") (pinfunction "CC2_B5") (pintype "passive"))
    )
    (net (code "240") (name "unconnected-(USB1-Pad1)") (class "Default")
      (node (ref "USB1") (pin "1") (pinfunction "1_1") (pintype "passive"))
    )
    (net (code "241") (name "unconnected-(USB1-SBU1-PadA8)") (class "Default")
      (node (ref "USB1") (pin "A8") (pinfunction "SBU1_A8") (pintype "passive"))
    )
    (net (code "242") (name "unconnected-(USB1-SBU2-PadB8)") (class "Default")
      (node (ref "USB1") (pin "B8") (pinfunction "SBU2_B8") (pintype "passive"))
    )
  )
)
